# SlowChans.net
KiCad netlist of a schematic drawn in Altium Designer
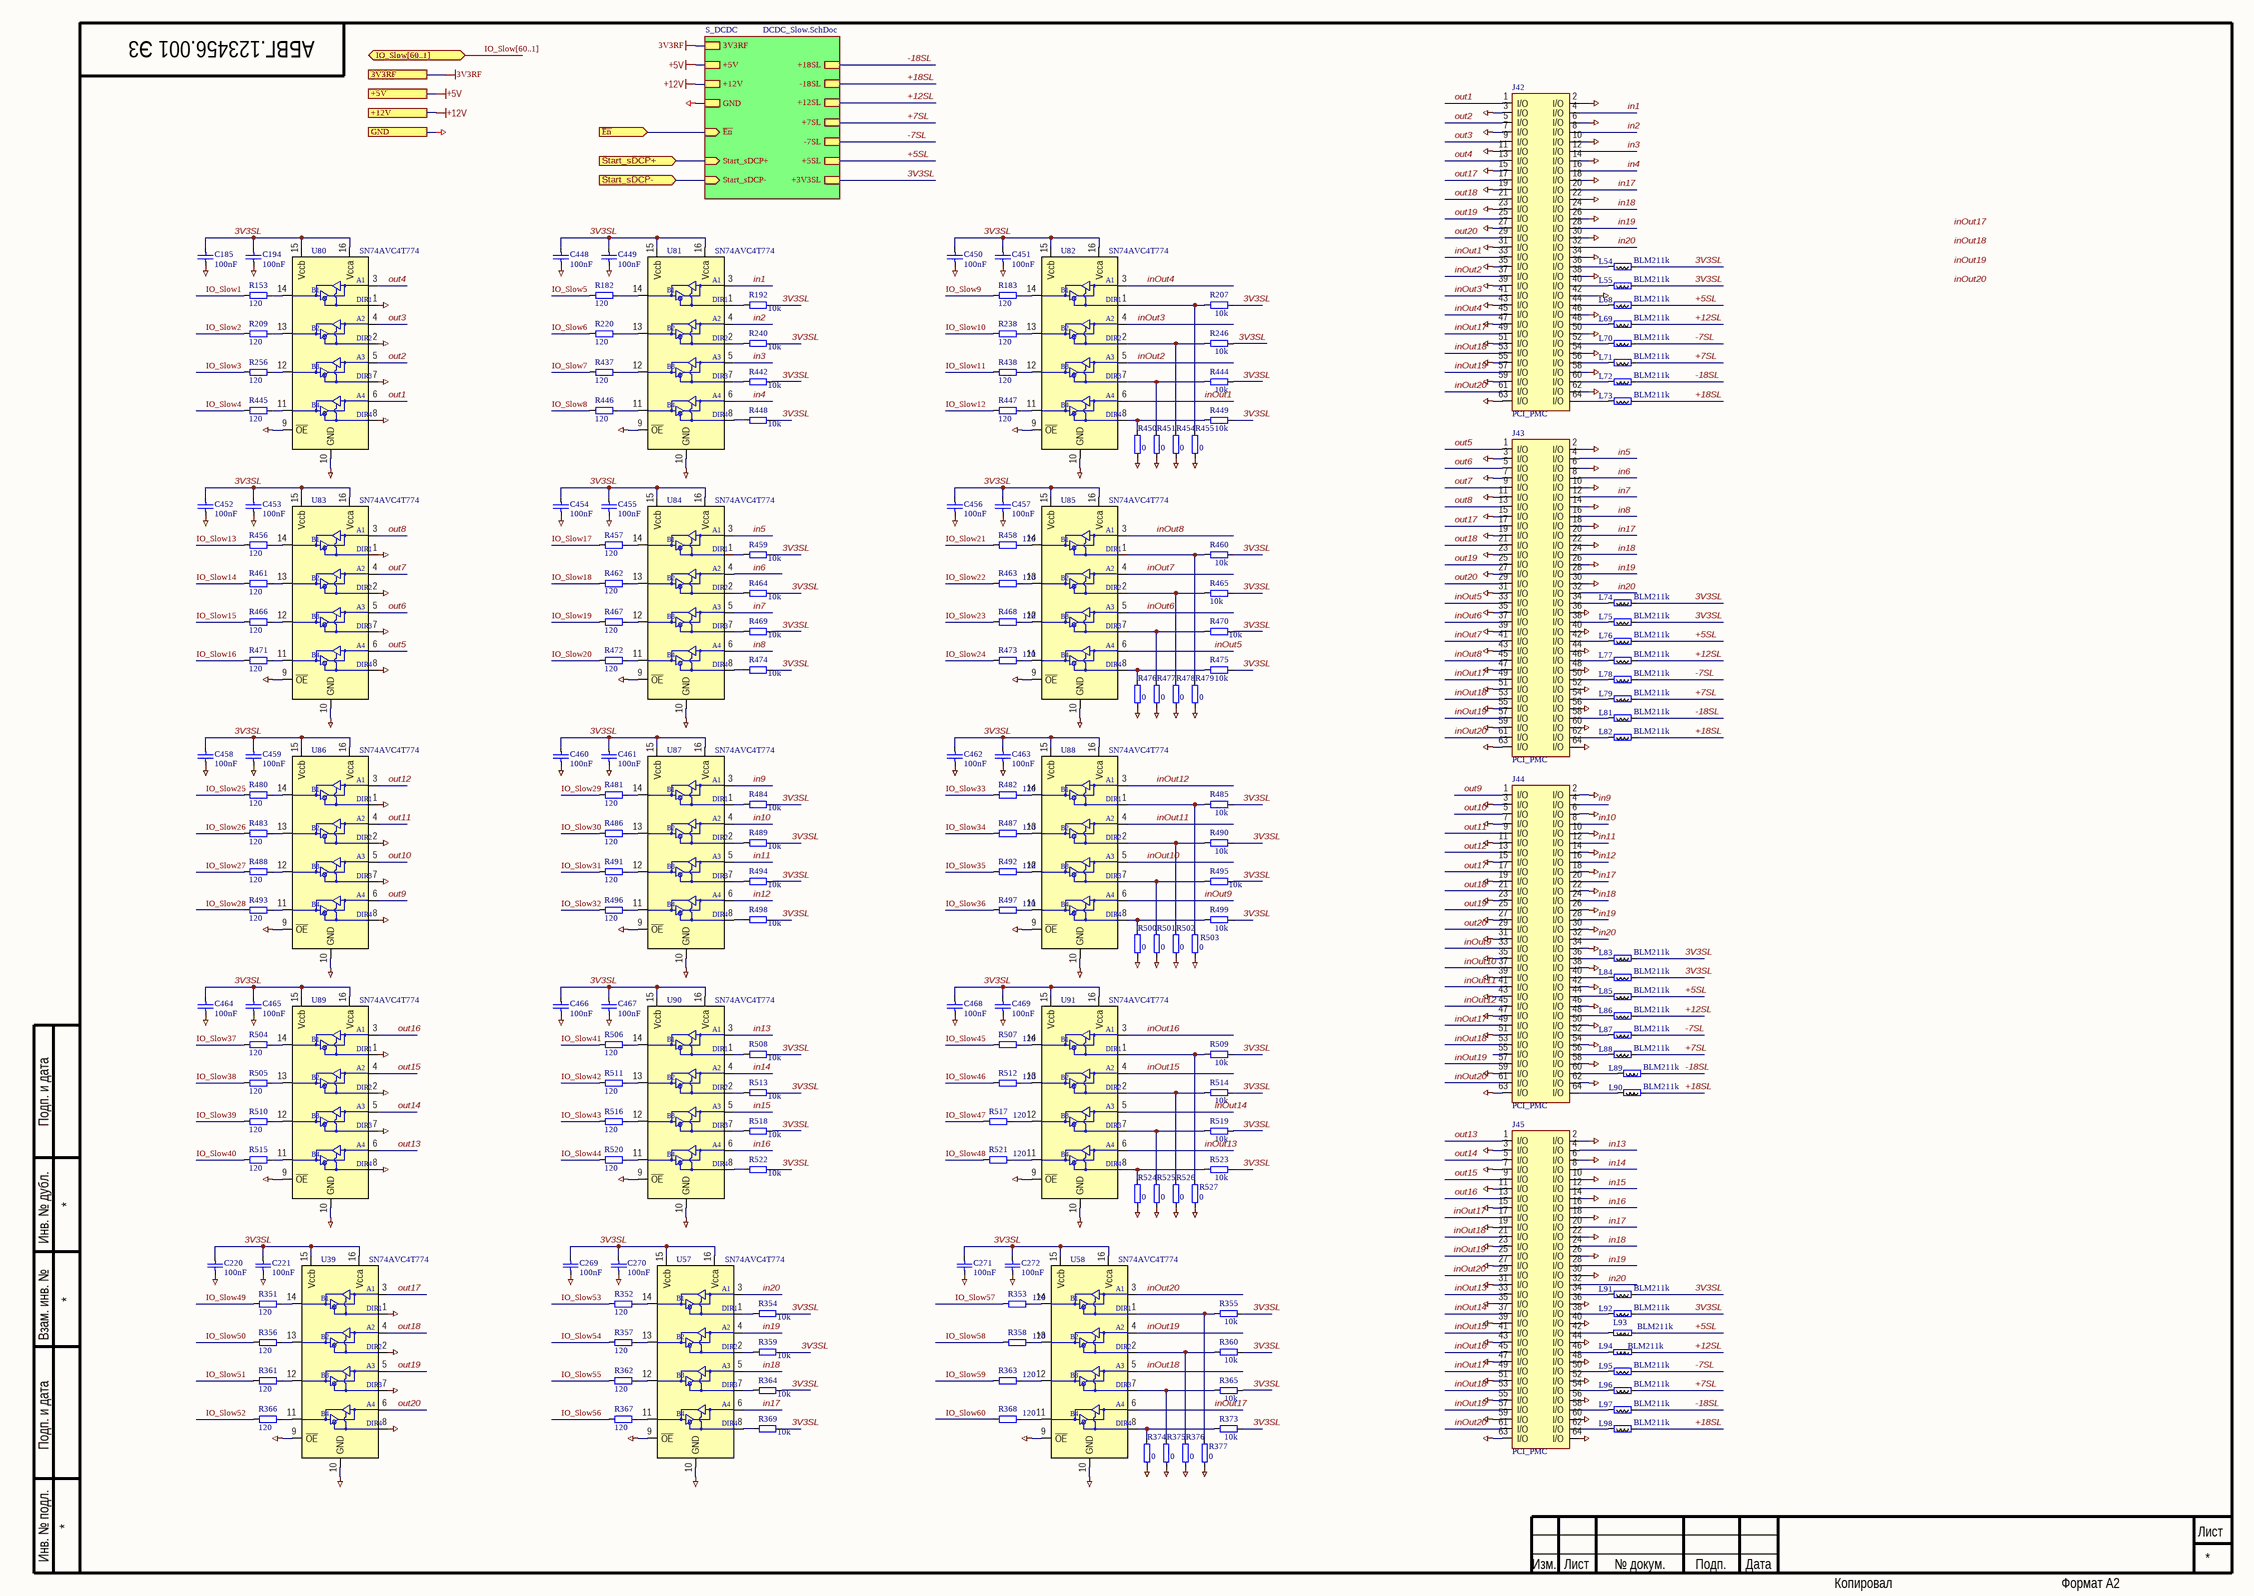
[diagram p0: SlowChans.SchDoc]

(export (version "E")
  (design (tool "Eeschema 10.0.6"))
  (components
    (comp (ref "C185")
      (value "100nF")
      (footprint "SMD0805CAP")
      (description "Чип конденсатор 0805")
      (fields (field (name "VOLTAGE") "25V") (field (name "TOLERANCE") "20%"))
      (libsource (lib "DDSintLib") (part "C0805"))
    )
    (comp (ref "C194")
      (value "100nF")
      (footprint "SMD0805CAP")
      (description "Чип конденсатор 0805")
      (fields (field (name "VOLTAGE") "25V") (field (name "TOLERANCE") "20%"))
      (libsource (lib "DDSintLib") (part "C0805"))
    )
    (comp (ref "C220")
      (value "100nF")
      (footprint "SMD0805CAP")
      (description "Чип конденсатор 0805")
      (fields (field (name "VOLTAGE") "25V") (field (name "TOLERANCE") "20%"))
      (libsource (lib "DDSintLib") (part "C0805"))
    )
    (comp (ref "C221")
      (value "100nF")
      (footprint "SMD0805CAP")
      (description "Чип конденсатор 0805")
      (fields (field (name "VOLTAGE") "25V") (field (name "TOLERANCE") "20%"))
      (libsource (lib "DDSintLib") (part "C0805"))
    )
    (comp (ref "C269")
      (value "100nF")
      (footprint "SMD0805CAP")
      (description "Чип конденсатор 0805")
      (fields (field (name "VOLTAGE") "25V") (field (name "TOLERANCE") "20%"))
      (libsource (lib "DDSintLib") (part "C0805"))
    )
    (comp (ref "C270")
      (value "100nF")
      (footprint "SMD0805CAP")
      (description "Чип конденсатор 0805")
      (fields (field (name "VOLTAGE") "25V") (field (name "TOLERANCE") "20%"))
      (libsource (lib "DDSintLib") (part "C0805"))
    )
    (comp (ref "C271")
      (value "100nF")
      (footprint "SMD0805CAP")
      (description "Чип конденсатор 0805")
      (fields (field (name "VOLTAGE") "25V") (field (name "TOLERANCE") "20%"))
      (libsource (lib "DDSintLib") (part "C0805"))
    )
    (comp (ref "C272")
      (value "100nF")
      (footprint "SMD0805CAP")
      (description "Чип конденсатор 0805")
      (fields (field (name "VOLTAGE") "25V") (field (name "TOLERANCE") "20%"))
      (libsource (lib "DDSintLib") (part "C0805"))
    )
    (comp (ref "C448")
      (value "100nF")
      (footprint "SMD0805CAP")
      (description "Чип конденсатор 0805")
      (fields (field (name "VOLTAGE") "25V") (field (name "TOLERANCE") "20%"))
      (libsource (lib "DDSintLib") (part "C0805"))
    )
    (comp (ref "C449")
      (value "100nF")
      (footprint "SMD0805CAP")
      (description "Чип конденсатор 0805")
      (fields (field (name "VOLTAGE") "25V") (field (name "TOLERANCE") "20%"))
      (libsource (lib "DDSintLib") (part "C0805"))
    )
    (comp (ref "C450")
      (value "100nF")
      (footprint "SMD0805CAP")
      (description "Чип конденсатор 0805")
      (fields (field (name "VOLTAGE") "25V") (field (name "TOLERANCE") "20%"))
      (libsource (lib "DDSintLib") (part "C0805"))
    )
    (comp (ref "C451")
      (value "100nF")
      (footprint "SMD0805CAP")
      (description "Чип конденсатор 0805")
      (fields (field (name "VOLTAGE") "25V") (field (name "TOLERANCE") "20%"))
      (libsource (lib "DDSintLib") (part "C0805"))
    )
    (comp (ref "C452")
      (value "100nF")
      (footprint "SMD0805CAP")
      (description "Чип конденсатор 0805")
      (fields (field (name "VOLTAGE") "25V") (field (name "TOLERANCE") "20%"))
      (libsource (lib "DDSintLib") (part "C0805"))
    )
    (comp (ref "C453")
      (value "100nF")
      (footprint "SMD0805CAP")
      (description "Чип конденсатор 0805")
      (fields (field (name "VOLTAGE") "25V") (field (name "TOLERANCE") "20%"))
      (libsource (lib "DDSintLib") (part "C0805"))
    )
    (comp (ref "C454")
      (value "100nF")
      (footprint "SMD0805CAP")
      (description "Чип конденсатор 0805")
      (fields (field (name "VOLTAGE") "25V") (field (name "TOLERANCE") "20%"))
      (libsource (lib "DDSintLib") (part "C0805"))
    )
    (comp (ref "C455")
      (value "100nF")
      (footprint "SMD0805CAP")
      (description "Чип конденсатор 0805")
      (fields (field (name "VOLTAGE") "25V") (field (name "TOLERANCE") "20%"))
      (libsource (lib "DDSintLib") (part "C0805"))
    )
    (comp (ref "C456")
      (value "100nF")
      (footprint "SMD0805CAP")
      (description "Чип конденсатор 0805")
      (fields (field (name "VOLTAGE") "25V") (field (name "TOLERANCE") "20%"))
      (libsource (lib "DDSintLib") (part "C0805"))
    )
    (comp (ref "C457")
      (value "100nF")
      (footprint "SMD0805CAP")
      (description "Чип конденсатор 0805")
      (fields (field (name "VOLTAGE") "25V") (field (name "TOLERANCE") "20%"))
      (libsource (lib "DDSintLib") (part "C0805"))
    )
    (comp (ref "C458")
      (value "100nF")
      (footprint "SMD0805CAP")
      (description "Чип конденсатор 0805")
      (fields (field (name "VOLTAGE") "25V") (field (name "TOLERANCE") "20%"))
      (libsource (lib "DDSintLib") (part "C0805"))
    )
    (comp (ref "C459")
      (value "100nF")
      (footprint "SMD0805CAP")
      (description "Чип конденсатор 0805")
      (fields (field (name "VOLTAGE") "25V") (field (name "TOLERANCE") "20%"))
      (libsource (lib "DDSintLib") (part "C0805"))
    )
    (comp (ref "C460")
      (value "100nF")
      (footprint "SMD0805CAP")
      (description "Чип конденсатор 0805")
      (fields (field (name "VOLTAGE") "25V") (field (name "TOLERANCE") "20%"))
      (libsource (lib "DDSintLib") (part "C0805"))
    )
    (comp (ref "C461")
      (value "100nF")
      (footprint "SMD0805CAP")
      (description "Чип конденсатор 0805")
      (fields (field (name "VOLTAGE") "25V") (field (name "TOLERANCE") "20%"))
      (libsource (lib "DDSintLib") (part "C0805"))
    )
    (comp (ref "C462")
      (value "100nF")
      (footprint "SMD0805CAP")
      (description "Чип конденсатор 0805")
      (fields (field (name "VOLTAGE") "25V") (field (name "TOLERANCE") "20%"))
      (libsource (lib "DDSintLib") (part "C0805"))
    )
    (comp (ref "C463")
      (value "100nF")
      (footprint "SMD0805CAP")
      (description "Чип конденсатор 0805")
      (fields (field (name "VOLTAGE") "25V") (field (name "TOLERANCE") "20%"))
      (libsource (lib "DDSintLib") (part "C0805"))
    )
    (comp (ref "C464")
      (value "100nF")
      (footprint "SMD0805CAP")
      (description "Чип конденсатор 0805")
      (fields (field (name "VOLTAGE") "25V") (field (name "TOLERANCE") "20%"))
      (libsource (lib "DDSintLib") (part "C0805"))
    )
    (comp (ref "C465")
      (value "100nF")
      (footprint "SMD0805CAP")
      (description "Чип конденсатор 0805")
      (fields (field (name "VOLTAGE") "25V") (field (name "TOLERANCE") "20%"))
      (libsource (lib "DDSintLib") (part "C0805"))
    )
    (comp (ref "C466")
      (value "100nF")
      (footprint "SMD0805CAP")
      (description "Чип конденсатор 0805")
      (fields (field (name "VOLTAGE") "25V") (field (name "TOLERANCE") "20%"))
      (libsource (lib "DDSintLib") (part "C0805"))
    )
    (comp (ref "C467")
      (value "100nF")
      (footprint "SMD0805CAP")
      (description "Чип конденсатор 0805")
      (fields (field (name "VOLTAGE") "25V") (field (name "TOLERANCE") "20%"))
      (libsource (lib "DDSintLib") (part "C0805"))
    )
    (comp (ref "C468")
      (value "100nF")
      (footprint "SMD0805CAP")
      (description "Чип конденсатор 0805")
      (fields (field (name "VOLTAGE") "25V") (field (name "TOLERANCE") "20%"))
      (libsource (lib "DDSintLib") (part "C0805"))
    )
    (comp (ref "C469")
      (value "100nF")
      (footprint "SMD0805CAP")
      (description "Чип конденсатор 0805")
      (fields (field (name "VOLTAGE") "25V") (field (name "TOLERANCE") "20%"))
      (libsource (lib "DDSintLib") (part "C0805"))
    )
    (comp (ref "J42")
      (value "PCI_PMC")
      (footprint "TYCO_120521-1")
      (description "PCI Mezzanine Connector; IEEE 1386 MainBoard")
      (libsource (lib "DDSintLib") (part "PCI_PMC_M"))
    )
    (comp (ref "J43")
      (value "PCI_PMC")
      (footprint "TYCO_120521-1")
      (description "PCI Mezzanine Connector; IEEE 1386 MainBoard")
      (libsource (lib "DDSintLib") (part "PCI_PMC_M"))
    )
    (comp (ref "J44")
      (value "PCI_PMC")
      (footprint "TYCO_120521-1")
      (description "PCI Mezzanine Connector; IEEE 1386 MainBoard")
      (libsource (lib "DDSintLib") (part "PCI_PMC_M"))
    )
    (comp (ref "J45")
      (value "PCI_PMC")
      (footprint "TYCO_120521-1")
      (description "PCI Mezzanine Connector; IEEE 1386 MainBoard")
      (libsource (lib "DDSintLib") (part "PCI_PMC_M"))
    )
    (comp (ref "L54")
      (value "BLM211k")
      (footprint "RESC2012X50N")
      (description "SMD Ferrite bead 0805")
      (libsource (lib "DDSintLib") (part "BLM21"))
    )
    (comp (ref "L55")
      (value "BLM211k")
      (footprint "RESC2012X50N")
      (description "SMD Ferrite bead 0805")
      (libsource (lib "DDSintLib") (part "BLM21"))
    )
    (comp (ref "L68")
      (value "BLM211k")
      (footprint "RESC2012X50N")
      (description "SMD Ferrite bead 0805")
      (libsource (lib "DDSintLib") (part "BLM21"))
    )
    (comp (ref "L69")
      (value "BLM211k")
      (footprint "RESC2012X50N")
      (description "SMD Ferrite bead 0805")
      (libsource (lib "DDSintLib") (part "BLM21"))
    )
    (comp (ref "L70")
      (value "BLM211k")
      (footprint "RESC2012X50N")
      (description "SMD Ferrite bead 0805")
      (libsource (lib "DDSintLib") (part "BLM21"))
    )
    (comp (ref "L71")
      (value "BLM211k")
      (footprint "RESC2012X50N")
      (description "SMD Ferrite bead 0805")
      (libsource (lib "DDSintLib") (part "BLM21"))
    )
    (comp (ref "L72")
      (value "BLM211k")
      (footprint "RESC2012X50N")
      (description "SMD Ferrite bead 0805")
      (libsource (lib "DDSintLib") (part "BLM21"))
    )
    (comp (ref "L73")
      (value "BLM211k")
      (footprint "RESC2012X50N")
      (description "SMD Ferrite bead 0805")
      (libsource (lib "DDSintLib") (part "BLM21"))
    )
    (comp (ref "L74")
      (value "BLM211k")
      (footprint "RESC2012X50N")
      (description "SMD Ferrite bead 0805")
      (libsource (lib "DDSintLib") (part "BLM21"))
    )
    (comp (ref "L75")
      (value "BLM211k")
      (footprint "RESC2012X50N")
      (description "SMD Ferrite bead 0805")
      (libsource (lib "DDSintLib") (part "BLM21"))
    )
    (comp (ref "L76")
      (value "BLM211k")
      (footprint "RESC2012X50N")
      (description "SMD Ferrite bead 0805")
      (libsource (lib "DDSintLib") (part "BLM21"))
    )
    (comp (ref "L77")
      (value "BLM211k")
      (footprint "RESC2012X50N")
      (description "SMD Ferrite bead 0805")
      (libsource (lib "DDSintLib") (part "BLM21"))
    )
    (comp (ref "L78")
      (value "BLM211k")
      (footprint "RESC2012X50N")
      (description "SMD Ferrite bead 0805")
      (libsource (lib "DDSintLib") (part "BLM21"))
    )
    (comp (ref "L79")
      (value "BLM211k")
      (footprint "RESC2012X50N")
      (description "SMD Ferrite bead 0805")
      (libsource (lib "DDSintLib") (part "BLM21"))
    )
    (comp (ref "L81")
      (value "BLM211k")
      (footprint "RESC2012X50N")
      (description "SMD Ferrite bead 0805")
      (libsource (lib "DDSintLib") (part "BLM21"))
    )
    (comp (ref "L82")
      (value "BLM211k")
      (footprint "RESC2012X50N")
      (description "SMD Ferrite bead 0805")
      (libsource (lib "DDSintLib") (part "BLM21"))
    )
    (comp (ref "L83")
      (value "BLM211k")
      (footprint "RESC2012X50N")
      (description "SMD Ferrite bead 0805")
      (libsource (lib "DDSintLib") (part "BLM21"))
    )
    (comp (ref "L84")
      (value "BLM211k")
      (footprint "RESC2012X50N")
      (description "SMD Ferrite bead 0805")
      (libsource (lib "DDSintLib") (part "BLM21"))
    )
    (comp (ref "L85")
      (value "BLM211k")
      (footprint "RESC2012X50N")
      (description "SMD Ferrite bead 0805")
      (libsource (lib "DDSintLib") (part "BLM21"))
    )
    (comp (ref "L86")
      (value "BLM211k")
      (footprint "RESC2012X50N")
      (description "SMD Ferrite bead 0805")
      (libsource (lib "DDSintLib") (part "BLM21"))
    )
    (comp (ref "L87")
      (value "BLM211k")
      (footprint "RESC2012X50N")
      (description "SMD Ferrite bead 0805")
      (libsource (lib "DDSintLib") (part "BLM21"))
    )
    (comp (ref "L88")
      (value "BLM211k")
      (footprint "RESC2012X50N")
      (description "SMD Ferrite bead 0805")
      (libsource (lib "DDSintLib") (part "BLM21"))
    )
    (comp (ref "L89")
      (value "BLM211k")
      (footprint "RESC2012X50N")
      (description "SMD Ferrite bead 0805")
      (libsource (lib "DDSintLib") (part "BLM21"))
    )
    (comp (ref "L90")
      (value "BLM211k")
      (footprint "RESC2012X50N")
      (description "SMD Ferrite bead 0805")
      (libsource (lib "DDSintLib") (part "BLM21"))
    )
    (comp (ref "L91")
      (value "BLM211k")
      (footprint "RESC2012X50N")
      (description "SMD Ferrite bead 0805")
      (libsource (lib "DDSintLib") (part "BLM21"))
    )
    (comp (ref "L92")
      (value "BLM211k")
      (footprint "RESC2012X50N")
      (description "SMD Ferrite bead 0805")
      (libsource (lib "DDSintLib") (part "BLM21"))
    )
    (comp (ref "L93")
      (value "BLM211k")
      (footprint "RESC2012X50N")
      (description "SMD Ferrite bead 0805")
      (libsource (lib "") (part "BLM21_1"))
    )
    (comp (ref "L94")
      (value "BLM211k")
      (footprint "RESC2012X50N")
      (description "SMD Ferrite bead 0805")
      (libsource (lib "") (part "BLM21_1"))
    )
    (comp (ref "L95")
      (value "BLM211k")
      (footprint "RESC2012X50N")
      (description "SMD Ferrite bead 0805")
      (libsource (lib "DDSintLib") (part "BLM21"))
    )
    (comp (ref "L96")
      (value "BLM211k")
      (footprint "RESC2012X50N")
      (description "SMD Ferrite bead 0805")
      (libsource (lib "DDSintLib") (part "BLM21"))
    )
    (comp (ref "L97")
      (value "BLM211k")
      (footprint "RESC2012X50N")
      (description "SMD Ferrite bead 0805")
      (libsource (lib "DDSintLib") (part "BLM21"))
    )
    (comp (ref "L98")
      (value "BLM211k")
      (footprint "RESC2012X50N")
      (description "SMD Ferrite bead 0805")
      (libsource (lib "DDSintLib") (part "BLM21"))
    )
    (comp (ref "R153")
      (value "120")
      (footprint "SMD0805RES")
      (description "Чип резистор 0805")
      (fields (field (name "TOLERANCE") "1%"))
      (libsource (lib "DDSintLib") (part "R0805"))
    )
    (comp (ref "R182")
      (value "120")
      (footprint "SMD0805RES")
      (description "Чип резистор 0805")
      (fields (field (name "TOLERANCE") "1%"))
      (libsource (lib "DDSintLib") (part "R0805"))
    )
    (comp (ref "R183")
      (value "120")
      (footprint "SMD0805RES")
      (description "Чип резистор 0805")
      (fields (field (name "TOLERANCE") "1%"))
      (libsource (lib "DDSintLib") (part "R0805"))
    )
    (comp (ref "R192")
      (value "10k")
      (footprint "SMD0805RES")
      (description "Чип резистор 0805")
      (fields (field (name "TOLERANCE") "1%"))
      (libsource (lib "DDSintLib") (part "R0805"))
    )
    (comp (ref "R207")
      (value "10k")
      (footprint "SMD0805RES")
      (description "Чип резистор 0805")
      (fields (field (name "TOLERANCE") "1%"))
      (libsource (lib "DDSintLib") (part "R0805"))
    )
    (comp (ref "R209")
      (value "120")
      (footprint "SMD0805RES")
      (description "Чип резистор 0805")
      (fields (field (name "TOLERANCE") "1%"))
      (libsource (lib "DDSintLib") (part "R0805"))
    )
    (comp (ref "R220")
      (value "120")
      (footprint "SMD0805RES")
      (description "Чип резистор 0805")
      (fields (field (name "TOLERANCE") "1%"))
      (libsource (lib "DDSintLib") (part "R0805"))
    )
    (comp (ref "R238")
      (value "120")
      (footprint "SMD0805RES")
      (description "Чип резистор 0805")
      (fields (field (name "TOLERANCE") "1%"))
      (libsource (lib "DDSintLib") (part "R0805"))
    )
    (comp (ref "R240")
      (value "10k")
      (footprint "SMD0805RES")
      (description "Чип резистор 0805")
      (fields (field (name "TOLERANCE") "1%"))
      (libsource (lib "DDSintLib") (part "R0805"))
    )
    (comp (ref "R246")
      (value "10k")
      (footprint "SMD0805RES")
      (description "Чип резистор 0805")
      (fields (field (name "TOLERANCE") "1%"))
      (libsource (lib "DDSintLib") (part "R0805"))
    )
    (comp (ref "R256")
      (value "120")
      (footprint "SMD0805RES")
      (description "Чип резистор 0805")
      (fields (field (name "TOLERANCE") "1%"))
      (libsource (lib "DDSintLib") (part "R0805"))
    )
    (comp (ref "R351")
      (value "120")
      (footprint "SMD0805RES")
      (description "Чип резистор 0805")
      (fields (field (name "TOLERANCE") "1%"))
      (libsource (lib "DDSintLib") (part "R0805"))
    )
    (comp (ref "R352")
      (value "120")
      (footprint "SMD0805RES")
      (description "Чип резистор 0805")
      (fields (field (name "TOLERANCE") "1%"))
      (libsource (lib "DDSintLib") (part "R0805"))
    )
    (comp (ref "R353")
      (value "120")
      (footprint "SMD0805RES")
      (description "Чип резистор 0805")
      (fields (field (name "TOLERANCE") "1%"))
      (libsource (lib "DDSintLib") (part "R0805"))
    )
    (comp (ref "R354")
      (value "10k")
      (footprint "SMD0805RES")
      (description "Чип резистор 0805")
      (fields (field (name "TOLERANCE") "1%"))
      (libsource (lib "DDSintLib") (part "R0805"))
    )
    (comp (ref "R355")
      (value "10k")
      (footprint "SMD0805RES")
      (description "Чип резистор 0805")
      (fields (field (name "TOLERANCE") "1%"))
      (libsource (lib "DDSintLib") (part "R0805"))
    )
    (comp (ref "R356")
      (value "120")
      (footprint "SMD0805RES")
      (description "Чип резистор 0805")
      (fields (field (name "TOLERANCE") "1%"))
      (libsource (lib "DDSintLib") (part "R0805"))
    )
    (comp (ref "R357")
      (value "120")
      (footprint "SMD0805RES")
      (description "Чип резистор 0805")
      (fields (field (name "TOLERANCE") "1%"))
      (libsource (lib "DDSintLib") (part "R0805"))
    )
    (comp (ref "R358")
      (value "120")
      (footprint "SMD0805RES")
      (description "Чип резистор 0805")
      (fields (field (name "TOLERANCE") "1%"))
      (libsource (lib "DDSintLib") (part "R0805"))
    )
    (comp (ref "R359")
      (value "10k")
      (footprint "SMD0805RES")
      (description "Чип резистор 0805")
      (fields (field (name "TOLERANCE") "1%"))
      (libsource (lib "DDSintLib") (part "R0805"))
    )
    (comp (ref "R360")
      (value "10k")
      (footprint "SMD0805RES")
      (description "Чип резистор 0805")
      (fields (field (name "TOLERANCE") "1%"))
      (libsource (lib "DDSintLib") (part "R0805"))
    )
    (comp (ref "R361")
      (value "120")
      (footprint "SMD0805RES")
      (description "Чип резистор 0805")
      (fields (field (name "TOLERANCE") "1%"))
      (libsource (lib "DDSintLib") (part "R0805"))
    )
    (comp (ref "R362")
      (value "120")
      (footprint "SMD0805RES")
      (description "Чип резистор 0805")
      (fields (field (name "TOLERANCE") "1%"))
      (libsource (lib "DDSintLib") (part "R0805"))
    )
    (comp (ref "R363")
      (value "120")
      (footprint "SMD0805RES")
      (description "Чип резистор 0805")
      (fields (field (name "TOLERANCE") "1%"))
      (libsource (lib "DDSintLib") (part "R0805"))
    )
    (comp (ref "R364")
      (value "10k")
      (footprint "SMD0805RES")
      (description "Чип резистор 0805")
      (fields (field (name "TOLERANCE") "1%"))
      (libsource (lib "DDSintLib") (part "R0805"))
    )
    (comp (ref "R365")
      (value "10k")
      (footprint "SMD0805RES")
      (description "Чип резистор 0805")
      (fields (field (name "TOLERANCE") "1%"))
      (libsource (lib "DDSintLib") (part "R0805"))
    )
    (comp (ref "R366")
      (value "120")
      (footprint "SMD0805RES")
      (description "Чип резистор 0805")
      (fields (field (name "TOLERANCE") "1%"))
      (libsource (lib "DDSintLib") (part "R0805"))
    )
    (comp (ref "R367")
      (value "120")
      (footprint "SMD0805RES")
      (description "Чип резистор 0805")
      (fields (field (name "TOLERANCE") "1%"))
      (libsource (lib "DDSintLib") (part "R0805"))
    )
    (comp (ref "R368")
      (value "120")
      (footprint "SMD0805RES")
      (description "Чип резистор 0805")
      (fields (field (name "TOLERANCE") "1%"))
      (libsource (lib "DDSintLib") (part "R0805"))
    )
    (comp (ref "R369")
      (value "10k")
      (footprint "SMD0805RES")
      (description "Чип резистор 0805")
      (fields (field (name "TOLERANCE") "1%"))
      (libsource (lib "DDSintLib") (part "R0805"))
    )
    (comp (ref "R373")
      (value "10k")
      (footprint "SMD0805RES")
      (description "Чип резистор 0805")
      (fields (field (name "TOLERANCE") "1%"))
      (libsource (lib "DDSintLib") (part "R0805"))
    )
    (comp (ref "R374")
      (value "0")
      (footprint "SMD0805RES")
      (description "Чип резистор 0805")
      (fields (field (name "TOLERANCE") "1%"))
      (libsource (lib "DDSintLib") (part "R0805"))
    )
    (comp (ref "R375")
      (value "0")
      (footprint "SMD0805RES")
      (description "Чип резистор 0805")
      (fields (field (name "TOLERANCE") "1%"))
      (libsource (lib "DDSintLib") (part "R0805"))
    )
    (comp (ref "R376")
      (value "0")
      (footprint "SMD0805RES")
      (description "Чип резистор 0805")
      (fields (field (name "TOLERANCE") "1%"))
      (libsource (lib "DDSintLib") (part "R0805"))
    )
    (comp (ref "R377")
      (value "0")
      (footprint "SMD0805RES")
      (description "Чип резистор 0805")
      (fields (field (name "TOLERANCE") "1%"))
      (libsource (lib "DDSintLib") (part "R0805"))
    )
    (comp (ref "R437")
      (value "120")
      (footprint "SMD0805RES")
      (description "Чип резистор 0805")
      (fields (field (name "TOLERANCE") "1%"))
      (libsource (lib "DDSintLib") (part "R0805"))
    )
    (comp (ref "R438")
      (value "120")
      (footprint "SMD0805RES")
      (description "Чип резистор 0805")
      (fields (field (name "TOLERANCE") "1%"))
      (libsource (lib "DDSintLib") (part "R0805"))
    )
    (comp (ref "R442")
      (value "10k")
      (footprint "SMD0805RES")
      (description "Чип резистор 0805")
      (fields (field (name "TOLERANCE") "1%"))
      (libsource (lib "DDSintLib") (part "R0805"))
    )
    (comp (ref "R444")
      (value "10k")
      (footprint "SMD0805RES")
      (description "Чип резистор 0805")
      (fields (field (name "TOLERANCE") "1%"))
      (libsource (lib "DDSintLib") (part "R0805"))
    )
    (comp (ref "R445")
      (value "120")
      (footprint "SMD0805RES")
      (description "Чип резистор 0805")
      (fields (field (name "TOLERANCE") "1%"))
      (libsource (lib "DDSintLib") (part "R0805"))
    )
    (comp (ref "R446")
      (value "120")
      (footprint "SMD0805RES")
      (description "Чип резистор 0805")
      (fields (field (name "TOLERANCE") "1%"))
      (libsource (lib "DDSintLib") (part "R0805"))
    )
    (comp (ref "R447")
      (value "120")
      (footprint "SMD0805RES")
      (description "Чип резистор 0805")
      (fields (field (name "TOLERANCE") "1%"))
      (libsource (lib "DDSintLib") (part "R0805"))
    )
    (comp (ref "R448")
      (value "10k")
      (footprint "SMD0805RES")
      (description "Чип резистор 0805")
      (fields (field (name "TOLERANCE") "1%"))
      (libsource (lib "DDSintLib") (part "R0805"))
    )
    (comp (ref "R449")
      (value "10k")
      (footprint "SMD0805RES")
      (description "Чип резистор 0805")
      (fields (field (name "TOLERANCE") "1%"))
      (libsource (lib "DDSintLib") (part "R0805"))
    )
    (comp (ref "R450")
      (value "0")
      (footprint "SMD0805RES")
      (description "Чип резистор 0805")
      (fields (field (name "TOLERANCE") "1%"))
      (libsource (lib "DDSintLib") (part "R0805"))
    )
    (comp (ref "R451")
      (value "0")
      (footprint "SMD0805RES")
      (description "Чип резистор 0805")
      (fields (field (name "TOLERANCE") "1%"))
      (libsource (lib "DDSintLib") (part "R0805"))
    )
    (comp (ref "R454")
      (value "0")
      (footprint "SMD0805RES")
      (description "Чип резистор 0805")
      (fields (field (name "TOLERANCE") "1%"))
      (libsource (lib "DDSintLib") (part "R0805"))
    )
    (comp (ref "R455")
      (value "0")
      (footprint "SMD0805RES")
      (description "Чип резистор 0805")
      (fields (field (name "TOLERANCE") "1%"))
      (libsource (lib "DDSintLib") (part "R0805"))
    )
    (comp (ref "R456")
      (value "120")
      (footprint "SMD0805RES")
      (description "Чип резистор 0805")
      (fields (field (name "TOLERANCE") "1%"))
      (libsource (lib "DDSintLib") (part "R0805"))
    )
    (comp (ref "R457")
      (value "120")
      (footprint "SMD0805RES")
      (description "Чип резистор 0805")
      (fields (field (name "TOLERANCE") "1%"))
      (libsource (lib "DDSintLib") (part "R0805"))
    )
    (comp (ref "R458")
      (value "120")
      (footprint "SMD0805RES")
      (description "Чип резистор 0805")
      (fields (field (name "TOLERANCE") "1%"))
      (libsource (lib "DDSintLib") (part "R0805"))
    )
    (comp (ref "R459")
      (value "10k")
      (footprint "SMD0805RES")
      (description "Чип резистор 0805")
      (fields (field (name "TOLERANCE") "1%"))
      (libsource (lib "DDSintLib") (part "R0805"))
    )
    (comp (ref "R460")
      (value "10k")
      (footprint "SMD0805RES")
      (description "Чип резистор 0805")
      (fields (field (name "TOLERANCE") "1%"))
      (libsource (lib "DDSintLib") (part "R0805"))
    )
    (comp (ref "R461")
      (value "120")
      (footprint "SMD0805RES")
      (description "Чип резистор 0805")
      (fields (field (name "TOLERANCE") "1%"))
      (libsource (lib "DDSintLib") (part "R0805"))
    )
    (comp (ref "R462")
      (value "120")
      (footprint "SMD0805RES")
      (description "Чип резистор 0805")
      (fields (field (name "TOLERANCE") "1%"))
      (libsource (lib "DDSintLib") (part "R0805"))
    )
    (comp (ref "R463")
      (value "120")
      (footprint "SMD0805RES")
      (description "Чип резистор 0805")
      (fields (field (name "TOLERANCE") "1%"))
      (libsource (lib "DDSintLib") (part "R0805"))
    )
    (comp (ref "R464")
      (value "10k")
      (footprint "SMD0805RES")
      (description "Чип резистор 0805")
      (fields (field (name "TOLERANCE") "1%"))
      (libsource (lib "DDSintLib") (part "R0805"))
    )
    (comp (ref "R465")
      (value "10k")
      (footprint "SMD0805RES")
      (description "Чип резистор 0805")
      (fields (field (name "TOLERANCE") "1%"))
      (libsource (lib "DDSintLib") (part "R0805"))
    )
    (comp (ref "R466")
      (value "120")
      (footprint "SMD0805RES")
      (description "Чип резистор 0805")
      (fields (field (name "TOLERANCE") "1%"))
      (libsource (lib "DDSintLib") (part "R0805"))
    )
    (comp (ref "R467")
      (value "120")
      (footprint "SMD0805RES")
      (description "Чип резистор 0805")
      (fields (field (name "TOLERANCE") "1%"))
      (libsource (lib "DDSintLib") (part "R0805"))
    )
    (comp (ref "R468")
      (value "120")
      (footprint "SMD0805RES")
      (description "Чип резистор 0805")
      (fields (field (name "TOLERANCE") "1%"))
      (libsource (lib "DDSintLib") (part "R0805"))
    )
    (comp (ref "R469")
      (value "10k")
      (footprint "SMD0805RES")
      (description "Чип резистор 0805")
      (fields (field (name "TOLERANCE") "1%"))
      (libsource (lib "DDSintLib") (part "R0805"))
    )
    (comp (ref "R470")
      (value "10k")
      (footprint "SMD0805RES")
      (description "Чип резистор 0805")
      (fields (field (name "TOLERANCE") "1%"))
      (libsource (lib "DDSintLib") (part "R0805"))
    )
    (comp (ref "R471")
      (value "120")
      (footprint "SMD0805RES")
      (description "Чип резистор 0805")
      (fields (field (name "TOLERANCE") "1%"))
      (libsource (lib "DDSintLib") (part "R0805"))
    )
    (comp (ref "R472")
      (value "120")
      (footprint "SMD0805RES")
      (description "Чип резистор 0805")
      (fields (field (name "TOLERANCE") "1%"))
      (libsource (lib "DDSintLib") (part "R0805"))
    )
    (comp (ref "R473")
      (value "120")
      (footprint "SMD0805RES")
      (description "Чип резистор 0805")
      (fields (field (name "TOLERANCE") "1%"))
      (libsource (lib "DDSintLib") (part "R0805"))
    )
    (comp (ref "R474")
      (value "10k")
      (footprint "SMD0805RES")
      (description "Чип резистор 0805")
      (fields (field (name "TOLERANCE") "1%"))
      (libsource (lib "DDSintLib") (part "R0805"))
    )
    (comp (ref "R475")
      (value "10k")
      (footprint "SMD0805RES")
      (description "Чип резистор 0805")
      (fields (field (name "TOLERANCE") "1%"))
      (libsource (lib "DDSintLib") (part "R0805"))
    )
    (comp (ref "R476")
      (value "0")
      (footprint "SMD0805RES")
      (description "Чип резистор 0805")
      (fields (field (name "TOLERANCE") "1%"))
      (libsource (lib "DDSintLib") (part "R0805"))
    )
    (comp (ref "R477")
      (value "0")
      (footprint "SMD0805RES")
      (description "Чип резистор 0805")
      (fields (field (name "TOLERANCE") "1%"))
      (libsource (lib "DDSintLib") (part "R0805"))
    )
    (comp (ref "R478")
      (value "0")
      (footprint "SMD0805RES")
      (description "Чип резистор 0805")
      (fields (field (name "TOLERANCE") "1%"))
      (libsource (lib "DDSintLib") (part "R0805"))
    )
    (comp (ref "R479")
      (value "0")
      (footprint "SMD0805RES")
      (description "Чип резистор 0805")
      (fields (field (name "TOLERANCE") "1%"))
      (libsource (lib "DDSintLib") (part "R0805"))
    )
    (comp (ref "R480")
      (value "120")
      (footprint "SMD0805RES")
      (description "Чип резистор 0805")
      (fields (field (name "TOLERANCE") "1%"))
      (libsource (lib "DDSintLib") (part "R0805"))
    )
    (comp (ref "R481")
      (value "120")
      (footprint "SMD0805RES")
      (description "Чип резистор 0805")
      (fields (field (name "TOLERANCE") "1%"))
      (libsource (lib "DDSintLib") (part "R0805"))
    )
    (comp (ref "R482")
      (value "120")
      (footprint "SMD0805RES")
      (description "Чип резистор 0805")
      (fields (field (name "TOLERANCE") "1%"))
      (libsource (lib "DDSintLib") (part "R0805"))
    )
    (comp (ref "R483")
      (value "120")
      (footprint "SMD0805RES")
      (description "Чип резистор 0805")
      (fields (field (name "TOLERANCE") "1%"))
      (libsource (lib "DDSintLib") (part "R0805"))
    )
    (comp (ref "R484")
      (value "10k")
      (footprint "SMD0805RES")
      (description "Чип резистор 0805")
      (fields (field (name "TOLERANCE") "1%"))
      (libsource (lib "DDSintLib") (part "R0805"))
    )
    (comp (ref "R485")
      (value "10k")
      (footprint "SMD0805RES")
      (description "Чип резистор 0805")
      (fields (field (name "TOLERANCE") "1%"))
      (libsource (lib "DDSintLib") (part "R0805"))
    )
    (comp (ref "R486")
      (value "120")
      (footprint "SMD0805RES")
      (description "Чип резистор 0805")
      (fields (field (name "TOLERANCE") "1%"))
      (libsource (lib "DDSintLib") (part "R0805"))
    )
    (comp (ref "R487")
      (value "120")
      (footprint "SMD0805RES")
      (description "Чип резистор 0805")
      (fields (field (name "TOLERANCE") "1%"))
      (libsource (lib "DDSintLib") (part "R0805"))
    )
    (comp (ref "R488")
      (value "120")
      (footprint "SMD0805RES")
      (description "Чип резистор 0805")
      (fields (field (name "TOLERANCE") "1%"))
      (libsource (lib "DDSintLib") (part "R0805"))
    )
    (comp (ref "R489")
      (value "10k")
      (footprint "SMD0805RES")
      (description "Чип резистор 0805")
      (fields (field (name "TOLERANCE") "1%"))
      (libsource (lib "DDSintLib") (part "R0805"))
    )
    (comp (ref "R490")
      (value "10k")
      (footprint "SMD0805RES")
      (description "Чип резистор 0805")
      (fields (field (name "TOLERANCE") "1%"))
      (libsource (lib "DDSintLib") (part "R0805"))
    )
    (comp (ref "R491")
      (value "120")
      (footprint "SMD0805RES")
      (description "Чип резистор 0805")
      (fields (field (name "TOLERANCE") "1%"))
      (libsource (lib "DDSintLib") (part "R0805"))
    )
    (comp (ref "R492")
      (value "120")
      (footprint "SMD0805RES")
      (description "Чип резистор 0805")
      (fields (field (name "TOLERANCE") "1%"))
      (libsource (lib "DDSintLib") (part "R0805"))
    )
    (comp (ref "R493")
      (value "120")
      (footprint "SMD0805RES")
      (description "Чип резистор 0805")
      (fields (field (name "TOLERANCE") "1%"))
      (libsource (lib "DDSintLib") (part "R0805"))
    )
    (comp (ref "R494")
      (value "10k")
      (footprint "SMD0805RES")
      (description "Чип резистор 0805")
      (fields (field (name "TOLERANCE") "1%"))
      (libsource (lib "DDSintLib") (part "R0805"))
    )
    (comp (ref "R495")
      (value "10k")
      (footprint "SMD0805RES")
      (description "Чип резистор 0805")
      (fields (field (name "TOLERANCE") "1%"))
      (libsource (lib "DDSintLib") (part "R0805"))
    )
    (comp (ref "R496")
      (value "120")
      (footprint "SMD0805RES")
      (description "Чип резистор 0805")
      (fields (field (name "TOLERANCE") "1%"))
      (libsource (lib "DDSintLib") (part "R0805"))
    )
    (comp (ref "R497")
      (value "120")
      (footprint "SMD0805RES")
      (description "Чип резистор 0805")
      (fields (field (name "TOLERANCE") "1%"))
      (libsource (lib "DDSintLib") (part "R0805"))
    )
    (comp (ref "R498")
      (value "10k")
      (footprint "SMD0805RES")
      (description "Чип резистор 0805")
      (fields (field (name "TOLERANCE") "1%"))
      (libsource (lib "DDSintLib") (part "R0805"))
    )
    (comp (ref "R499")
      (value "10k")
      (footprint "SMD0805RES")
      (description "Чип резистор 0805")
      (fields (field (name "TOLERANCE") "1%"))
      (libsource (lib "DDSintLib") (part "R0805"))
    )
    (comp (ref "R500")
      (value "0")
      (footprint "SMD0805RES")
      (description "Чип резистор 0805")
      (fields (field (name "TOLERANCE") "1%"))
      (libsource (lib "DDSintLib") (part "R0805"))
    )
    (comp (ref "R501")
      (value "0")
      (footprint "SMD0805RES")
      (description "Чип резистор 0805")
      (fields (field (name "TOLERANCE") "1%"))
      (libsource (lib "DDSintLib") (part "R0805"))
    )
    (comp (ref "R502")
      (value "0")
      (footprint "SMD0805RES")
      (description "Чип резистор 0805")
      (fields (field (name "TOLERANCE") "1%"))
      (libsource (lib "DDSintLib") (part "R0805"))
    )
    (comp (ref "R503")
      (value "0")
      (footprint "SMD0805RES")
      (description "Чип резистор 0805")
      (fields (field (name "TOLERANCE") "1%"))
      (libsource (lib "DDSintLib") (part "R0805"))
    )
    (comp (ref "R504")
      (value "120")
      (footprint "SMD0805RES")
      (description "Чип резистор 0805")
      (fields (field (name "TOLERANCE") "1%"))
      (libsource (lib "DDSintLib") (part "R0805"))
    )
    (comp (ref "R505")
      (value "120")
      (footprint "SMD0805RES")
      (description "Чип резистор 0805")
      (fields (field (name "TOLERANCE") "1%"))
      (libsource (lib "DDSintLib") (part "R0805"))
    )
    (comp (ref "R506")
      (value "120")
      (footprint "SMD0805RES")
      (description "Чип резистор 0805")
      (fields (field (name "TOLERANCE") "1%"))
      (libsource (lib "DDSintLib") (part "R0805"))
    )
    (comp (ref "R507")
      (value "120")
      (footprint "SMD0805RES")
      (description "Чип резистор 0805")
      (fields (field (name "TOLERANCE") "1%"))
      (libsource (lib "DDSintLib") (part "R0805"))
    )
    (comp (ref "R508")
      (value "10k")
      (footprint "SMD0805RES")
      (description "Чип резистор 0805")
      (fields (field (name "TOLERANCE") "1%"))
      (libsource (lib "DDSintLib") (part "R0805"))
    )
    (comp (ref "R509")
      (value "10k")
      (footprint "SMD0805RES")
      (description "Чип резистор 0805")
      (fields (field (name "TOLERANCE") "1%"))
      (libsource (lib "DDSintLib") (part "R0805"))
    )
    (comp (ref "R510")
      (value "120")
      (footprint "SMD0805RES")
      (description "Чип резистор 0805")
      (fields (field (name "TOLERANCE") "1%"))
      (libsource (lib "DDSintLib") (part "R0805"))
    )
    (comp (ref "R511")
      (value "120")
      (footprint "SMD0805RES")
      (description "Чип резистор 0805")
      (fields (field (name "TOLERANCE") "1%"))
      (libsource (lib "DDSintLib") (part "R0805"))
    )
    (comp (ref "R512")
      (value "120")
      (footprint "SMD0805RES")
      (description "Чип резистор 0805")
      (fields (field (name "TOLERANCE") "1%"))
      (libsource (lib "DDSintLib") (part "R0805"))
    )
    (comp (ref "R513")
      (value "10k")
      (footprint "SMD0805RES")
      (description "Чип резистор 0805")
      (fields (field (name "TOLERANCE") "1%"))
      (libsource (lib "DDSintLib") (part "R0805"))
    )
    (comp (ref "R514")
      (value "10k")
      (footprint "SMD0805RES")
      (description "Чип резистор 0805")
      (fields (field (name "TOLERANCE") "1%"))
      (libsource (lib "DDSintLib") (part "R0805"))
    )
    (comp (ref "R515")
      (value "120")
      (footprint "SMD0805RES")
      (description "Чип резистор 0805")
      (fields (field (name "TOLERANCE") "1%"))
      (libsource (lib "DDSintLib") (part "R0805"))
    )
    (comp (ref "R516")
      (value "120")
      (footprint "SMD0805RES")
      (description "Чип резистор 0805")
      (fields (field (name "TOLERANCE") "1%"))
      (libsource (lib "DDSintLib") (part "R0805"))
    )
    (comp (ref "R517")
      (value "120")
      (footprint "SMD0805RES")
      (description "Чип резистор 0805")
      (fields (field (name "TOLERANCE") "1%"))
      (libsource (lib "DDSintLib") (part "R0805"))
    )
    (comp (ref "R518")
      (value "10k")
      (footprint "SMD0805RES")
      (description "Чип резистор 0805")
      (fields (field (name "TOLERANCE") "1%"))
      (libsource (lib "DDSintLib") (part "R0805"))
    )
    (comp (ref "R519")
      (value "10k")
      (footprint "SMD0805RES")
      (description "Чип резистор 0805")
      (fields (field (name "TOLERANCE") "1%"))
      (libsource (lib "DDSintLib") (part "R0805"))
    )
    (comp (ref "R520")
      (value "120")
      (footprint "SMD0805RES")
      (description "Чип резистор 0805")
      (fields (field (name "TOLERANCE") "1%"))
      (libsource (lib "DDSintLib") (part "R0805"))
    )
    (comp (ref "R521")
      (value "120")
      (footprint "SMD0805RES")
      (description "Чип резистор 0805")
      (fields (field (name "TOLERANCE") "1%"))
      (libsource (lib "DDSintLib") (part "R0805"))
    )
    (comp (ref "R522")
      (value "10k")
      (footprint "SMD0805RES")
      (description "Чип резистор 0805")
      (fields (field (name "TOLERANCE") "1%"))
      (libsource (lib "DDSintLib") (part "R0805"))
    )
    (comp (ref "R523")
      (value "10k")
      (footprint "SMD0805RES")
      (description "Чип резистор 0805")
      (fields (field (name "TOLERANCE") "1%"))
      (libsource (lib "DDSintLib") (part "R0805"))
    )
    (comp (ref "R524")
      (value "0")
      (footprint "SMD0805RES")
      (description "Чип резистор 0805")
      (fields (field (name "TOLERANCE") "1%"))
      (libsource (lib "DDSintLib") (part "R0805"))
    )
    (comp (ref "R525")
      (value "0")
      (footprint "SMD0805RES")
      (description "Чип резистор 0805")
      (fields (field (name "TOLERANCE") "1%"))
      (libsource (lib "DDSintLib") (part "R0805"))
    )
    (comp (ref "R526")
      (value "0")
      (footprint "SMD0805RES")
      (description "Чип резистор 0805")
      (fields (field (name "TOLERANCE") "1%"))
      (libsource (lib "DDSintLib") (part "R0805"))
    )
    (comp (ref "R527")
      (value "0")
      (footprint "SMD0805RES")
      (description "Чип резистор 0805")
      (fields (field (name "TOLERANCE") "1%"))
      (libsource (lib "DDSintLib") (part "R0805"))
    )
    (comp (ref "U39")
      (value "SN74AVC4T774")
      (footprint "TSSOP-16")
      (description "Двунаправленный буфер")
      (fields (field (name "VOLTAGE") "1V1.. 3.6V  I/Os are 4.6-V Tolerant"))
      (libsource (lib "DDS1") (part "SN74AVC4T774"))
    )
    (comp (ref "U57")
      (value "SN74AVC4T774")
      (footprint "TSSOP-16")
      (description "Двунаправленный буфер")
      (fields (field (name "VOLTAGE") "1V1.. 3.6V  I/Os are 4.6-V Tolerant"))
      (libsource (lib "DDS1") (part "SN74AVC4T774"))
    )
    (comp (ref "U58")
      (value "SN74AVC4T774")
      (footprint "TSSOP-16")
      (description "Двунаправленный буфер")
      (fields (field (name "VOLTAGE") "1V1.. 3.6V  I/Os are 4.6-V Tolerant"))
      (libsource (lib "DDS1") (part "SN74AVC4T774"))
    )
    (comp (ref "U80")
      (value "SN74AVC4T774")
      (footprint "TSSOP-16")
      (description "Двунаправленный буфер")
      (fields (field (name "VOLTAGE") "1V1.. 3.6V  I/Os are 4.6-V Tolerant"))
      (libsource (lib "DDS1") (part "SN74AVC4T774"))
    )
    (comp (ref "U81")
      (value "SN74AVC4T774")
      (footprint "TSSOP-16")
      (description "Двунаправленный буфер")
      (fields (field (name "VOLTAGE") "1V1.. 3.6V  I/Os are 4.6-V Tolerant"))
      (libsource (lib "DDS1") (part "SN74AVC4T774"))
    )
    (comp (ref "U82")
      (value "SN74AVC4T774")
      (footprint "TSSOP-16")
      (description "Двунаправленный буфер")
      (fields (field (name "VOLTAGE") "1V1.. 3.6V  I/Os are 4.6-V Tolerant"))
      (libsource (lib "DDS1") (part "SN74AVC4T774"))
    )
    (comp (ref "U83")
      (value "SN74AVC4T774")
      (footprint "TSSOP-16")
      (description "Двунаправленный буфер")
      (fields (field (name "VOLTAGE") "1V1.. 3.6V  I/Os are 4.6-V Tolerant"))
      (libsource (lib "DDS1") (part "SN74AVC4T774"))
    )
    (comp (ref "U84")
      (value "SN74AVC4T774")
      (footprint "TSSOP-16")
      (description "Двунаправленный буфер")
      (fields (field (name "VOLTAGE") "1V1.. 3.6V  I/Os are 4.6-V Tolerant"))
      (libsource (lib "DDS1") (part "SN74AVC4T774"))
    )
    (comp (ref "U85")
      (value "SN74AVC4T774")
      (footprint "TSSOP-16")
      (description "Двунаправленный буфер")
      (fields (field (name "VOLTAGE") "1V1.. 3.6V  I/Os are 4.6-V Tolerant"))
      (libsource (lib "DDS1") (part "SN74AVC4T774"))
    )
    (comp (ref "U86")
      (value "SN74AVC4T774")
      (footprint "TSSOP-16")
      (description "Двунаправленный буфер")
      (fields (field (name "VOLTAGE") "1V1.. 3.6V  I/Os are 4.6-V Tolerant"))
      (libsource (lib "DDS1") (part "SN74AVC4T774"))
    )
    (comp (ref "U87")
      (value "SN74AVC4T774")
      (footprint "TSSOP-16")
      (description "Двунаправленный буфер")
      (fields (field (name "VOLTAGE") "1V1.. 3.6V  I/Os are 4.6-V Tolerant"))
      (libsource (lib "DDS1") (part "SN74AVC4T774"))
    )
    (comp (ref "U88")
      (value "SN74AVC4T774")
      (footprint "TSSOP-16")
      (description "Двунаправленный буфер")
      (fields (field (name "VOLTAGE") "1V1.. 3.6V  I/Os are 4.6-V Tolerant"))
      (libsource (lib "DDS1") (part "SN74AVC4T774"))
    )
    (comp (ref "U89")
      (value "SN74AVC4T774")
      (footprint "TSSOP-16")
      (description "Двунаправленный буфер")
      (fields (field (name "VOLTAGE") "1V1.. 3.6V  I/Os are 4.6-V Tolerant"))
      (libsource (lib "DDS1") (part "SN74AVC4T774"))
    )
    (comp (ref "U90")
      (value "SN74AVC4T774")
      (footprint "TSSOP-16")
      (description "Двунаправленный буфер")
      (fields (field (name "VOLTAGE") "1V1.. 3.6V  I/Os are 4.6-V Tolerant"))
      (libsource (lib "DDS1") (part "SN74AVC4T774"))
    )
    (comp (ref "U91")
      (value "SN74AVC4T774")
      (footprint "TSSOP-16")
      (description "Двунаправленный буфер")
      (fields (field (name "VOLTAGE") "1V1.. 3.6V  I/Os are 4.6-V Tolerant"))
      (libsource (lib "DDS1") (part "SN74AVC4T774"))
    )
  )
  (nets
    (net (code "3") (name "/+5SL") (class "Default")
      (node (ref "L68") (pin "2") (pinfunction "2_2") (pintype "passive"))
      (node (ref "L76") (pin "2") (pinfunction "2_2") (pintype "passive"))
      (node (ref "L85") (pin "2") (pinfunction "2_2") (pintype "passive"))
      (node (ref "L93") (pin "1") (pinfunction "1_1") (pintype "passive"))
    )
    (net (code "4") (name "/+7SL") (class "Default")
      (node (ref "L71") (pin "2") (pinfunction "2_2") (pintype "passive"))
      (node (ref "L79") (pin "2") (pinfunction "2_2") (pintype "passive"))
      (node (ref "L88") (pin "2") (pinfunction "2_2") (pintype "passive"))
      (node (ref "L96") (pin "2") (pinfunction "2_2") (pintype "passive"))
    )
    (net (code "5") (name "/+12SL") (class "Default")
      (node (ref "L69") (pin "2") (pinfunction "2_2") (pintype "passive"))
      (node (ref "L77") (pin "2") (pinfunction "2_2") (pintype "passive"))
      (node (ref "L86") (pin "2") (pinfunction "2_2") (pintype "passive"))
      (node (ref "L94") (pin "1") (pinfunction "1_1") (pintype "passive"))
    )
    (net (code "6") (name "/+18SL") (class "Default")
      (node (ref "L73") (pin "2") (pinfunction "2_2") (pintype "passive"))
      (node (ref "L82") (pin "2") (pinfunction "2_2") (pintype "passive"))
      (node (ref "L90") (pin "2") (pinfunction "2_2") (pintype "passive"))
      (node (ref "L98") (pin "2") (pinfunction "2_2") (pintype "passive"))
    )
    (net (code "7") (name "/-7SL") (class "Default")
      (node (ref "L70") (pin "2") (pinfunction "2_2") (pintype "passive"))
      (node (ref "L78") (pin "2") (pinfunction "2_2") (pintype "passive"))
      (node (ref "L87") (pin "2") (pinfunction "2_2") (pintype "passive"))
      (node (ref "L95") (pin "2") (pinfunction "2_2") (pintype "passive"))
    )
    (net (code "8") (name "/-18SL") (class "Default")
      (node (ref "L72") (pin "2") (pinfunction "2_2") (pintype "passive"))
      (node (ref "L81") (pin "2") (pinfunction "2_2") (pintype "passive"))
      (node (ref "L89") (pin "2") (pinfunction "2_2") (pintype "passive"))
      (node (ref "L97") (pin "2") (pinfunction "2_2") (pintype "passive"))
    )
    (net (code "9") (name "/3V3SL") (class "Default")
      (node (ref "C185") (pin "2") (pinfunction "2_2") (pintype "passive"))
      (node (ref "C194") (pin "2") (pinfunction "2_2") (pintype "passive"))
      (node (ref "C220") (pin "2") (pinfunction "2_2") (pintype "passive"))
      (node (ref "C221") (pin "2") (pinfunction "2_2") (pintype "passive"))
      (node (ref "C269") (pin "2") (pinfunction "2_2") (pintype "passive"))
      (node (ref "C270") (pin "2") (pinfunction "2_2") (pintype "passive"))
      (node (ref "C271") (pin "2") (pinfunction "2_2") (pintype "passive"))
      (node (ref "C272") (pin "2") (pinfunction "2_2") (pintype "passive"))
      (node (ref "C448") (pin "2") (pinfunction "2_2") (pintype "passive"))
      (node (ref "C449") (pin "2") (pinfunction "2_2") (pintype "passive"))
      (node (ref "C450") (pin "2") (pinfunction "2_2") (pintype "passive"))
      (node (ref "C451") (pin "2") (pinfunction "2_2") (pintype "passive"))
      (node (ref "C452") (pin "2") (pinfunction "2_2") (pintype "passive"))
      (node (ref "C453") (pin "2") (pinfunction "2_2") (pintype "passive"))
      (node (ref "C454") (pin "2") (pinfunction "2_2") (pintype "passive"))
      (node (ref "C455") (pin "2") (pinfunction "2_2") (pintype "passive"))
      (node (ref "C456") (pin "2") (pinfunction "2_2") (pintype "passive"))
      (node (ref "C457") (pin "2") (pinfunction "2_2") (pintype "passive"))
      (node (ref "C458") (pin "2") (pinfunction "2_2") (pintype "passive"))
      (node (ref "C459") (pin "2") (pinfunction "2_2") (pintype "passive"))
      (node (ref "C460") (pin "2") (pinfunction "2_2") (pintype "passive"))
      (node (ref "C461") (pin "2") (pinfunction "2_2") (pintype "passive"))
      (node (ref "C462") (pin "2") (pinfunction "2_2") (pintype "passive"))
      (node (ref "C463") (pin "2") (pinfunction "2_2") (pintype "passive"))
      (node (ref "C464") (pin "2") (pinfunction "2_2") (pintype "passive"))
      (node (ref "C465") (pin "2") (pinfunction "2_2") (pintype "passive"))
      (node (ref "C466") (pin "2") (pinfunction "2_2") (pintype "passive"))
      (node (ref "C467") (pin "2") (pinfunction "2_2") (pintype "passive"))
      (node (ref "C468") (pin "2") (pinfunction "2_2") (pintype "passive"))
      (node (ref "C469") (pin "2") (pinfunction "2_2") (pintype "passive"))
      (node (ref "L54") (pin "2") (pinfunction "2_2") (pintype "passive"))
      (node (ref "L55") (pin "2") (pinfunction "2_2") (pintype "passive"))
      (node (ref "L74") (pin "2") (pinfunction "2_2") (pintype "passive"))
      (node (ref "L75") (pin "2") (pinfunction "2_2") (pintype "passive"))
      (node (ref "L83") (pin "2") (pinfunction "2_2") (pintype "passive"))
      (node (ref "L84") (pin "2") (pinfunction "2_2") (pintype "passive"))
      (node (ref "L91") (pin "2") (pinfunction "2_2") (pintype "passive"))
      (node (ref "L92") (pin "2") (pinfunction "2_2") (pintype "passive"))
      (node (ref "R192") (pin "1") (pinfunction "1_1") (pintype "passive"))
      (node (ref "R207") (pin "1") (pinfunction "1_1") (pintype "passive"))
      (node (ref "R240") (pin "1") (pinfunction "1_1") (pintype "passive"))
      (node (ref "R246") (pin "1") (pinfunction "1_1") (pintype "passive"))
      (node (ref "R354") (pin "1") (pinfunction "1_1") (pintype "passive"))
      (node (ref "R355") (pin "1") (pinfunction "1_1") (pintype "passive"))
      (node (ref "R359") (pin "1") (pinfunction "1_1") (pintype "passive"))
      (node (ref "R360") (pin "1") (pinfunction "1_1") (pintype "passive"))
      (node (ref "R364") (pin "1") (pinfunction "1_1") (pintype "passive"))
      (node (ref "R365") (pin "1") (pinfunction "1_1") (pintype "passive"))
      (node (ref "R369") (pin "1") (pinfunction "1_1") (pintype "passive"))
      (node (ref "R373") (pin "1") (pinfunction "1_1") (pintype "passive"))
      (node (ref "R442") (pin "1") (pinfunction "1_1") (pintype "passive"))
      (node (ref "R444") (pin "1") (pinfunction "1_1") (pintype "passive"))
      (node (ref "R448") (pin "1") (pinfunction "1_1") (pintype "passive"))
      (node (ref "R449") (pin "1") (pinfunction "1_1") (pintype "passive"))
      (node (ref "R459") (pin "1") (pinfunction "1_1") (pintype "passive"))
      (node (ref "R460") (pin "1") (pinfunction "1_1") (pintype "passive"))
      (node (ref "R464") (pin "1") (pinfunction "1_1") (pintype "passive"))
      (node (ref "R465") (pin "1") (pinfunction "1_1") (pintype "passive"))
      (node (ref "R469") (pin "1") (pinfunction "1_1") (pintype "passive"))
      (node (ref "R470") (pin "1") (pinfunction "1_1") (pintype "passive"))
      (node (ref "R474") (pin "1") (pinfunction "1_1") (pintype "passive"))
      (node (ref "R475") (pin "1") (pinfunction "1_1") (pintype "passive"))
      (node (ref "R484") (pin "1") (pinfunction "1_1") (pintype "passive"))
      (node (ref "R485") (pin "1") (pinfunction "1_1") (pintype "passive"))
      (node (ref "R489") (pin "1") (pinfunction "1_1") (pintype "passive"))
      (node (ref "R490") (pin "1") (pinfunction "1_1") (pintype "passive"))
      (node (ref "R494") (pin "1") (pinfunction "1_1") (pintype "passive"))
      (node (ref "R495") (pin "1") (pinfunction "1_1") (pintype "passive"))
      (node (ref "R498") (pin "1") (pinfunction "1_1") (pintype "passive"))
      (node (ref "R499") (pin "1") (pinfunction "1_1") (pintype "passive"))
      (node (ref "R508") (pin "1") (pinfunction "1_1") (pintype "passive"))
      (node (ref "R509") (pin "1") (pinfunction "1_1") (pintype "passive"))
      (node (ref "R513") (pin "1") (pinfunction "1_1") (pintype "passive"))
      (node (ref "R514") (pin "1") (pinfunction "1_1") (pintype "passive"))
      (node (ref "R518") (pin "1") (pinfunction "1_1") (pintype "passive"))
      (node (ref "R519") (pin "1") (pinfunction "1_1") (pintype "passive"))
      (node (ref "R522") (pin "1") (pinfunction "1_1") (pintype "passive"))
      (node (ref "R523") (pin "1") (pinfunction "1_1") (pintype "passive"))
      (node (ref "U39") (pin "15") (pinfunction "Vccb_15") (pintype "passive"))
      (node (ref "U39") (pin "16") (pinfunction "Vcca_16") (pintype "passive"))
      (node (ref "U57") (pin "15") (pinfunction "Vccb_15") (pintype "passive"))
      (node (ref "U57") (pin "16") (pinfunction "Vcca_16") (pintype "passive"))
      (node (ref "U58") (pin "15") (pinfunction "Vccb_15") (pintype "passive"))
      (node (ref "U58") (pin "16") (pinfunction "Vcca_16") (pintype "passive"))
      (node (ref "U80") (pin "15") (pinfunction "Vccb_15") (pintype "passive"))
      (node (ref "U80") (pin "16") (pinfunction "Vcca_16") (pintype "passive"))
      (node (ref "U81") (pin "15") (pinfunction "Vccb_15") (pintype "passive"))
      (node (ref "U81") (pin "16") (pinfunction "Vcca_16") (pintype "passive"))
      (node (ref "U82") (pin "15") (pinfunction "Vccb_15") (pintype "passive"))
      (node (ref "U82") (pin "16") (pinfunction "Vcca_16") (pintype "passive"))
      (node (ref "U83") (pin "15") (pinfunction "Vccb_15") (pintype "passive"))
      (node (ref "U83") (pin "16") (pinfunction "Vcca_16") (pintype "passive"))
      (node (ref "U84") (pin "15") (pinfunction "Vccb_15") (pintype "passive"))
      (node (ref "U84") (pin "16") (pinfunction "Vcca_16") (pintype "passive"))
      (node (ref "U85") (pin "15") (pinfunction "Vccb_15") (pintype "passive"))
      (node (ref "U85") (pin "16") (pinfunction "Vcca_16") (pintype "passive"))
      (node (ref "U86") (pin "15") (pinfunction "Vccb_15") (pintype "passive"))
      (node (ref "U86") (pin "16") (pinfunction "Vcca_16") (pintype "passive"))
      (node (ref "U87") (pin "15") (pinfunction "Vccb_15") (pintype "passive"))
      (node (ref "U87") (pin "16") (pinfunction "Vcca_16") (pintype "passive"))
      (node (ref "U88") (pin "15") (pinfunction "Vccb_15") (pintype "passive"))
      (node (ref "U88") (pin "16") (pinfunction "Vcca_16") (pintype "passive"))
      (node (ref "U89") (pin "15") (pinfunction "Vccb_15") (pintype "passive"))
      (node (ref "U89") (pin "16") (pinfunction "Vcca_16") (pintype "passive"))
      (node (ref "U90") (pin "15") (pinfunction "Vccb_15") (pintype "passive"))
      (node (ref "U90") (pin "16") (pinfunction "Vcca_16") (pintype "passive"))
      (node (ref "U91") (pin "15") (pinfunction "Vccb_15") (pintype "passive"))
      (node (ref "U91") (pin "16") (pinfunction "Vcca_16") (pintype "passive"))
    )
    (net (code "11") (name "/IO_Slow1") (class "Default")
      (node (ref "R153") (pin "2") (pinfunction "2_2") (pintype "passive"))
    )
    (net (code "12") (name "/IO_Slow2") (class "Default")
      (node (ref "R209") (pin "2") (pinfunction "2_2") (pintype "passive"))
    )
    (net (code "13") (name "/IO_Slow3") (class "Default")
      (node (ref "R256") (pin "2") (pinfunction "2_2") (pintype "passive"))
    )
    (net (code "14") (name "/IO_Slow4") (class "Default")
      (node (ref "R445") (pin "2") (pinfunction "2_2") (pintype "passive"))
    )
    (net (code "15") (name "/IO_Slow5") (class "Default")
      (node (ref "R182") (pin "2") (pinfunction "2_2") (pintype "passive"))
    )
    (net (code "16") (name "/IO_Slow6") (class "Default")
      (node (ref "R220") (pin "2") (pinfunction "2_2") (pintype "passive"))
    )
    (net (code "17") (name "/IO_Slow7") (class "Default")
      (node (ref "R437") (pin "2") (pinfunction "2_2") (pintype "passive"))
    )
    (net (code "18") (name "/IO_Slow8") (class "Default")
      (node (ref "R446") (pin "2") (pinfunction "2_2") (pintype "passive"))
    )
    (net (code "19") (name "/IO_Slow9") (class "Default")
      (node (ref "R183") (pin "2") (pinfunction "2_2") (pintype "passive"))
    )
    (net (code "20") (name "/IO_Slow10") (class "Default")
      (node (ref "R238") (pin "2") (pinfunction "2_2") (pintype "passive"))
    )
    (net (code "21") (name "/IO_Slow11") (class "Default")
      (node (ref "R438") (pin "2") (pinfunction "2_2") (pintype "passive"))
    )
    (net (code "22") (name "/IO_Slow12") (class "Default")
      (node (ref "R447") (pin "2") (pinfunction "2_2") (pintype "passive"))
    )
    (net (code "23") (name "/IO_Slow13") (class "Default")
      (node (ref "R456") (pin "2") (pinfunction "2_2") (pintype "passive"))
    )
    (net (code "24") (name "/IO_Slow14") (class "Default")
      (node (ref "R461") (pin "2") (pinfunction "2_2") (pintype "passive"))
    )
    (net (code "25") (name "/IO_Slow15") (class "Default")
      (node (ref "R466") (pin "2") (pinfunction "2_2") (pintype "passive"))
    )
    (net (code "26") (name "/IO_Slow16") (class "Default")
      (node (ref "R471") (pin "2") (pinfunction "2_2") (pintype "passive"))
    )
    (net (code "27") (name "/IO_Slow17") (class "Default")
      (node (ref "R457") (pin "2") (pinfunction "2_2") (pintype "passive"))
    )
    (net (code "28") (name "/IO_Slow18") (class "Default")
      (node (ref "R462") (pin "1") (pinfunction "1_1") (pintype "passive"))
    )
    (net (code "29") (name "/IO_Slow19") (class "Default")
      (node (ref "R467") (pin "2") (pinfunction "2_2") (pintype "passive"))
    )
    (net (code "30") (name "/IO_Slow20") (class "Default")
      (node (ref "R472") (pin "2") (pinfunction "2_2") (pintype "passive"))
    )
    (net (code "31") (name "/IO_Slow21") (class "Default")
      (node (ref "R458") (pin "2") (pinfunction "2_2") (pintype "passive"))
    )
    (net (code "32") (name "/IO_Slow22") (class "Default")
      (node (ref "R463") (pin "2") (pinfunction "2_2") (pintype "passive"))
    )
    (net (code "33") (name "/IO_Slow23") (class "Default")
      (node (ref "R468") (pin "2") (pinfunction "2_2") (pintype "passive"))
    )
    (net (code "34") (name "/IO_Slow24") (class "Default")
      (node (ref "R473") (pin "2") (pinfunction "2_2") (pintype "passive"))
    )
    (net (code "35") (name "/IO_Slow25") (class "Default")
      (node (ref "R480") (pin "2") (pinfunction "2_2") (pintype "passive"))
    )
    (net (code "36") (name "/IO_Slow26") (class "Default")
      (node (ref "R483") (pin "2") (pinfunction "2_2") (pintype "passive"))
    )
    (net (code "37") (name "/IO_Slow27") (class "Default")
      (node (ref "R488") (pin "2") (pinfunction "2_2") (pintype "passive"))
    )
    (net (code "38") (name "/IO_Slow28") (class "Default")
      (node (ref "R493") (pin "2") (pinfunction "2_2") (pintype "passive"))
    )
    (net (code "39") (name "/IO_Slow29") (class "Default")
      (node (ref "R481") (pin "2") (pinfunction "2_2") (pintype "passive"))
    )
    (net (code "40") (name "/IO_Slow30") (class "Default")
      (node (ref "R486") (pin "2") (pinfunction "2_2") (pintype "passive"))
    )
    (net (code "41") (name "/IO_Slow31") (class "Default")
      (node (ref "R491") (pin "2") (pinfunction "2_2") (pintype "passive"))
    )
    (net (code "42") (name "/IO_Slow32") (class "Default")
      (node (ref "R496") (pin "2") (pinfunction "2_2") (pintype "passive"))
    )
    (net (code "43") (name "/IO_Slow33") (class "Default")
      (node (ref "R482") (pin "2") (pinfunction "2_2") (pintype "passive"))
    )
    (net (code "44") (name "/IO_Slow34") (class "Default")
      (node (ref "R487") (pin "2") (pinfunction "2_2") (pintype "passive"))
    )
    (net (code "45") (name "/IO_Slow35") (class "Default")
      (node (ref "R492") (pin "2") (pinfunction "2_2") (pintype "passive"))
    )
    (net (code "46") (name "/IO_Slow36") (class "Default")
      (node (ref "R497") (pin "2") (pinfunction "2_2") (pintype "passive"))
    )
    (net (code "47") (name "/IO_Slow37") (class "Default")
      (node (ref "R504") (pin "2") (pinfunction "2_2") (pintype "passive"))
    )
    (net (code "48") (name "/IO_Slow38") (class "Default")
      (node (ref "R505") (pin "2") (pinfunction "2_2") (pintype "passive"))
    )
    (net (code "49") (name "/IO_Slow39") (class "Default")
      (node (ref "R510") (pin "2") (pinfunction "2_2") (pintype "passive"))
    )
    (net (code "50") (name "/IO_Slow40") (class "Default")
      (node (ref "R515") (pin "2") (pinfunction "2_2") (pintype "passive"))
    )
    (net (code "51") (name "/IO_Slow41") (class "Default")
      (node (ref "R506") (pin "2") (pinfunction "2_2") (pintype "passive"))
    )
    (net (code "52") (name "/IO_Slow42") (class "Default")
      (node (ref "R511") (pin "2") (pinfunction "2_2") (pintype "passive"))
    )
    (net (code "53") (name "/IO_Slow43") (class "Default")
      (node (ref "R516") (pin "2") (pinfunction "2_2") (pintype "passive"))
    )
    (net (code "54") (name "/IO_Slow44") (class "Default")
      (node (ref "R520") (pin "2") (pinfunction "2_2") (pintype "passive"))
    )
    (net (code "55") (name "/IO_Slow45") (class "Default")
      (node (ref "R507") (pin "2") (pinfunction "2_2") (pintype "passive"))
    )
    (net (code "56") (name "/IO_Slow46") (class "Default")
      (node (ref "R512") (pin "2") (pinfunction "2_2") (pintype "passive"))
    )
    (net (code "57") (name "/IO_Slow47") (class "Default")
      (node (ref "R517") (pin "2") (pinfunction "2_2") (pintype "passive"))
    )
    (net (code "58") (name "/IO_Slow48") (class "Default")
      (node (ref "R521") (pin "2") (pinfunction "2_2") (pintype "passive"))
    )
    (net (code "59") (name "/IO_Slow49") (class "Default")
      (node (ref "R351") (pin "2") (pinfunction "2_2") (pintype "passive"))
    )
    (net (code "60") (name "/IO_Slow50") (class "Default")
      (node (ref "R356") (pin "2") (pinfunction "2_2") (pintype "passive"))
    )
    (net (code "61") (name "/IO_Slow51") (class "Default")
      (node (ref "R361") (pin "2") (pinfunction "2_2") (pintype "passive"))
    )
    (net (code "62") (name "/IO_Slow52") (class "Default")
      (node (ref "R366") (pin "2") (pinfunction "2_2") (pintype "passive"))
    )
    (net (code "63") (name "/IO_Slow53") (class "Default")
      (node (ref "R352") (pin "2") (pinfunction "2_2") (pintype "passive"))
    )
    (net (code "64") (name "/IO_Slow54") (class "Default")
      (node (ref "R357") (pin "2") (pinfunction "2_2") (pintype "passive"))
    )
    (net (code "65") (name "/IO_Slow55") (class "Default")
      (node (ref "R362") (pin "2") (pinfunction "2_2") (pintype "passive"))
    )
    (net (code "66") (name "/IO_Slow56") (class "Default")
      (node (ref "R367") (pin "2") (pinfunction "2_2") (pintype "passive"))
    )
    (net (code "67") (name "/IO_Slow57") (class "Default")
      (node (ref "R353") (pin "2") (pinfunction "2_2") (pintype "passive"))
    )
    (net (code "68") (name "/IO_Slow58") (class "Default")
      (node (ref "R358") (pin "2") (pinfunction "2_2") (pintype "passive"))
    )
    (net (code "69") (name "/IO_Slow59") (class "Default")
      (node (ref "R363") (pin "2") (pinfunction "2_2") (pintype "passive"))
    )
    (net (code "70") (name "/IO_Slow60") (class "Default")
      (node (ref "R368") (pin "2") (pinfunction "2_2") (pintype "passive"))
    )
    (net (code "74") (name "/in1") (class "Default")
      (node (ref "J42") (pin "4") (pinfunction "I/O_4") (pintype "bidirectional"))
      (node (ref "U81") (pin "3") (pinfunction "A1_3") (pintype "passive"))
    )
    (net (code "75") (name "/in2") (class "Default")
      (node (ref "J42") (pin "8") (pinfunction "I/O_8") (pintype "bidirectional"))
      (node (ref "U81") (pin "4") (pinfunction "A2_4") (pintype "passive"))
    )
    (net (code "76") (name "/in3") (class "Default")
      (node (ref "J42") (pin "12") (pinfunction "I/O_12") (pintype "bidirectional"))
      (node (ref "U81") (pin "5") (pinfunction "A3_5") (pintype "passive"))
    )
    (net (code "77") (name "/in4") (class "Default")
      (node (ref "J42") (pin "16") (pinfunction "I/O_16") (pintype "bidirectional"))
      (node (ref "U81") (pin "6") (pinfunction "A4_6") (pintype "passive"))
    )
    (net (code "78") (name "/in5") (class "Default")
      (node (ref "J43") (pin "4") (pinfunction "I/O_4") (pintype "bidirectional"))
      (node (ref "U84") (pin "3") (pinfunction "A1_3") (pintype "passive"))
    )
    (net (code "79") (name "/in6") (class "Default")
      (node (ref "J43") (pin "8") (pinfunction "I/O_8") (pintype "bidirectional"))
      (node (ref "U84") (pin "4") (pinfunction "A2_4") (pintype "passive"))
    )
    (net (code "80") (name "/in7") (class "Default")
      (node (ref "J43") (pin "12") (pinfunction "I/O_12") (pintype "bidirectional"))
      (node (ref "U84") (pin "5") (pinfunction "A3_5") (pintype "passive"))
    )
    (net (code "81") (name "/in8") (class "Default")
      (node (ref "J43") (pin "16") (pinfunction "I/O_16") (pintype "bidirectional"))
      (node (ref "U84") (pin "6") (pinfunction "A4_6") (pintype "passive"))
    )
    (net (code "82") (name "/in9") (class "Default")
      (node (ref "J44") (pin "4") (pinfunction "I/O_4") (pintype "bidirectional"))
      (node (ref "U87") (pin "3") (pinfunction "A1_3") (pintype "passive"))
    )
    (net (code "83") (name "/in10") (class "Default")
      (node (ref "J44") (pin "8") (pinfunction "I/O_8") (pintype "bidirectional"))
      (node (ref "U87") (pin "4") (pinfunction "A2_4") (pintype "passive"))
    )
    (net (code "84") (name "/in11") (class "Default")
      (node (ref "J44") (pin "12") (pinfunction "I/O_12") (pintype "bidirectional"))
      (node (ref "U87") (pin "5") (pinfunction "A3_5") (pintype "passive"))
    )
    (net (code "85") (name "/in12") (class "Default")
      (node (ref "J44") (pin "16") (pinfunction "I/O_16") (pintype "bidirectional"))
      (node (ref "U87") (pin "6") (pinfunction "A4_6") (pintype "passive"))
    )
    (net (code "86") (name "/in13") (class "Default")
      (node (ref "J45") (pin "4") (pinfunction "I/O_4") (pintype "bidirectional"))
      (node (ref "U90") (pin "3") (pinfunction "A1_3") (pintype "passive"))
    )
    (net (code "87") (name "/in14") (class "Default")
      (node (ref "J45") (pin "8") (pinfunction "I/O_8") (pintype "bidirectional"))
      (node (ref "U90") (pin "4") (pinfunction "A2_4") (pintype "passive"))
    )
    (net (code "88") (name "/in15") (class "Default")
      (node (ref "J45") (pin "12") (pinfunction "I/O_12") (pintype "bidirectional"))
      (node (ref "U90") (pin "5") (pinfunction "A3_5") (pintype "passive"))
    )
    (net (code "89") (name "/in16") (class "Default")
      (node (ref "J45") (pin "16") (pinfunction "I/O_16") (pintype "bidirectional"))
      (node (ref "U90") (pin "6") (pinfunction "A4_6") (pintype "passive"))
    )
    (net (code "90") (name "/in17") (class "Default")
      (node (ref "J42") (pin "20") (pinfunction "I/O_20") (pintype "bidirectional"))
      (node (ref "J43") (pin "20") (pinfunction "I/O_20") (pintype "bidirectional"))
      (node (ref "J44") (pin "20") (pinfunction "I/O_20") (pintype "bidirectional"))
      (node (ref "J45") (pin "20") (pinfunction "I/O_20") (pintype "bidirectional"))
      (node (ref "U57") (pin "6") (pinfunction "A4_6") (pintype "passive"))
    )
    (net (code "91") (name "/in18") (class "Default")
      (node (ref "J42") (pin "24") (pinfunction "I/O_24") (pintype "bidirectional"))
      (node (ref "J43") (pin "24") (pinfunction "I/O_24") (pintype "bidirectional"))
      (node (ref "J44") (pin "24") (pinfunction "I/O_24") (pintype "bidirectional"))
      (node (ref "J45") (pin "24") (pinfunction "I/O_24") (pintype "bidirectional"))
      (node (ref "U57") (pin "5") (pinfunction "A3_5") (pintype "passive"))
    )
    (net (code "92") (name "/in19") (class "Default")
      (node (ref "J42") (pin "28") (pinfunction "I/O_28") (pintype "bidirectional"))
      (node (ref "J43") (pin "28") (pinfunction "I/O_28") (pintype "bidirectional"))
      (node (ref "J44") (pin "28") (pinfunction "I/O_28") (pintype "bidirectional"))
      (node (ref "J45") (pin "28") (pinfunction "I/O_28") (pintype "bidirectional"))
      (node (ref "U57") (pin "4") (pinfunction "A2_4") (pintype "passive"))
    )
    (net (code "93") (name "/in20") (class "Default")
      (node (ref "J42") (pin "32") (pinfunction "I/O_32") (pintype "bidirectional"))
      (node (ref "J43") (pin "32") (pinfunction "I/O_32") (pintype "bidirectional"))
      (node (ref "J44") (pin "32") (pinfunction "I/O_32") (pintype "bidirectional"))
      (node (ref "J45") (pin "32") (pinfunction "I/O_32") (pintype "bidirectional"))
      (node (ref "U57") (pin "3") (pinfunction "A1_3") (pintype "passive"))
    )
    (net (code "94") (name "/inOut1") (class "Default")
      (node (ref "J42") (pin "33") (pinfunction "I/O_33") (pintype "bidirectional"))
      (node (ref "U82") (pin "6") (pinfunction "A4_6") (pintype "passive"))
    )
    (net (code "95") (name "/inOut2") (class "Default")
      (node (ref "J42") (pin "37") (pinfunction "I/O_37") (pintype "bidirectional"))
      (node (ref "U82") (pin "5") (pinfunction "A3_5") (pintype "passive"))
    )
    (net (code "96") (name "/inOut3") (class "Default")
      (node (ref "J42") (pin "41") (pinfunction "I/O_41") (pintype "bidirectional"))
      (node (ref "U82") (pin "4") (pinfunction "A2_4") (pintype "passive"))
    )
    (net (code "97") (name "/inOut4") (class "Default")
      (node (ref "J42") (pin "45") (pinfunction "I/O_45") (pintype "bidirectional"))
      (node (ref "U82") (pin "3") (pinfunction "A1_3") (pintype "passive"))
    )
    (net (code "98") (name "/inOut5") (class "Default")
      (node (ref "J43") (pin "33") (pinfunction "I/O_33") (pintype "bidirectional"))
      (node (ref "U85") (pin "6") (pinfunction "A4_6") (pintype "passive"))
    )
    (net (code "99") (name "/inOut6") (class "Default")
      (node (ref "J43") (pin "37") (pinfunction "I/O_37") (pintype "bidirectional"))
      (node (ref "U85") (pin "5") (pinfunction "A3_5") (pintype "passive"))
    )
    (net (code "100") (name "/inOut7") (class "Default")
      (node (ref "J43") (pin "41") (pinfunction "I/O_41") (pintype "bidirectional"))
      (node (ref "U85") (pin "4") (pinfunction "A2_4") (pintype "passive"))
    )
    (net (code "101") (name "/inOut8") (class "Default")
      (node (ref "J43") (pin "45") (pinfunction "I/O_45") (pintype "bidirectional"))
      (node (ref "U85") (pin "3") (pinfunction "A1_3") (pintype "passive"))
    )
    (net (code "102") (name "/inOut9") (class "Default")
      (node (ref "J44") (pin "33") (pinfunction "I/O_33") (pintype "bidirectional"))
      (node (ref "U88") (pin "6") (pinfunction "A4_6") (pintype "passive"))
    )
    (net (code "103") (name "/inOut10") (class "Default")
      (node (ref "J44") (pin "37") (pinfunction "I/O_37") (pintype "bidirectional"))
      (node (ref "U88") (pin "5") (pinfunction "A3_5") (pintype "passive"))
    )
    (net (code "104") (name "/inOut11") (class "Default")
      (node (ref "J44") (pin "41") (pinfunction "I/O_41") (pintype "bidirectional"))
      (node (ref "U88") (pin "4") (pinfunction "A2_4") (pintype "passive"))
    )
    (net (code "105") (name "/inOut12") (class "Default")
      (node (ref "J44") (pin "45") (pinfunction "I/O_45") (pintype "bidirectional"))
      (node (ref "U88") (pin "3") (pinfunction "A1_3") (pintype "passive"))
    )
    (net (code "106") (name "/inOut13") (class "Default")
      (node (ref "J45") (pin "33") (pinfunction "I/O_33") (pintype "bidirectional"))
      (node (ref "U91") (pin "6") (pinfunction "A4_6") (pintype "passive"))
    )
    (net (code "107") (name "/inOut14") (class "Default")
      (node (ref "J45") (pin "37") (pinfunction "I/O_37") (pintype "bidirectional"))
      (node (ref "U91") (pin "5") (pinfunction "A3_5") (pintype "passive"))
    )
    (net (code "108") (name "/inOut15") (class "Default")
      (node (ref "J45") (pin "41") (pinfunction "I/O_41") (pintype "bidirectional"))
      (node (ref "U91") (pin "4") (pinfunction "A2_4") (pintype "passive"))
    )
    (net (code "109") (name "/inOut16") (class "Default")
      (node (ref "J45") (pin "45") (pinfunction "I/O_45") (pintype "bidirectional"))
      (node (ref "U91") (pin "3") (pinfunction "A1_3") (pintype "passive"))
    )
    (net (code "110") (name "/inOut17") (class "Default")
      (node (ref "J42") (pin "49") (pinfunction "I/O_49") (pintype "bidirectional"))
      (node (ref "J43") (pin "49") (pinfunction "I/O_49") (pintype "bidirectional"))
      (node (ref "J44") (pin "49") (pinfunction "I/O_49") (pintype "bidirectional"))
      (node (ref "J45") (pin "17") (pinfunction "I/O_17") (pintype "bidirectional"))
      (node (ref "J45") (pin "49") (pinfunction "I/O_49") (pintype "bidirectional"))
      (node (ref "U58") (pin "6") (pinfunction "A4_6") (pintype "passive"))
    )
    (net (code "111") (name "/inOut18") (class "Default")
      (node (ref "J42") (pin "53") (pinfunction "I/O_53") (pintype "bidirectional"))
      (node (ref "J43") (pin "53") (pinfunction "I/O_53") (pintype "bidirectional"))
      (node (ref "J44") (pin "53") (pinfunction "I/O_53") (pintype "bidirectional"))
      (node (ref "J45") (pin "21") (pinfunction "I/O_21") (pintype "bidirectional"))
      (node (ref "J45") (pin "53") (pinfunction "I/O_53") (pintype "bidirectional"))
      (node (ref "U58") (pin "5") (pinfunction "A3_5") (pintype "passive"))
    )
    (net (code "112") (name "/inOut19") (class "Default")
      (node (ref "J42") (pin "57") (pinfunction "I/O_57") (pintype "bidirectional"))
      (node (ref "J43") (pin "57") (pinfunction "I/O_57") (pintype "bidirectional"))
      (node (ref "J44") (pin "57") (pinfunction "I/O_57") (pintype "bidirectional"))
      (node (ref "J45") (pin "25") (pinfunction "I/O_25") (pintype "bidirectional"))
      (node (ref "J45") (pin "57") (pinfunction "I/O_57") (pintype "bidirectional"))
      (node (ref "U58") (pin "4") (pinfunction "A2_4") (pintype "passive"))
    )
    (net (code "113") (name "/inOut20") (class "Default")
      (node (ref "J42") (pin "61") (pinfunction "I/O_61") (pintype "bidirectional"))
      (node (ref "J43") (pin "61") (pinfunction "I/O_61") (pintype "bidirectional"))
      (node (ref "J44") (pin "61") (pinfunction "I/O_61") (pintype "bidirectional"))
      (node (ref "J45") (pin "29") (pinfunction "I/O_29") (pintype "bidirectional"))
      (node (ref "J45") (pin "61") (pinfunction "I/O_61") (pintype "bidirectional"))
      (node (ref "U58") (pin "3") (pinfunction "A1_3") (pintype "passive"))
    )
    (net (code "114") (name "/out1") (class "Default")
      (node (ref "J42") (pin "1") (pinfunction "I/O_1") (pintype "bidirectional"))
      (node (ref "U80") (pin "6") (pinfunction "A4_6") (pintype "passive"))
    )
    (net (code "115") (name "/out2") (class "Default")
      (node (ref "J42") (pin "5") (pinfunction "I/O_5") (pintype "bidirectional"))
      (node (ref "U80") (pin "5") (pinfunction "A3_5") (pintype "passive"))
    )
    (net (code "116") (name "/out3") (class "Default")
      (node (ref "J42") (pin "9") (pinfunction "I/O_9") (pintype "bidirectional"))
      (node (ref "U80") (pin "4") (pinfunction "A2_4") (pintype "passive"))
    )
    (net (code "117") (name "/out4") (class "Default")
      (node (ref "J42") (pin "13") (pinfunction "I/O_13") (pintype "bidirectional"))
      (node (ref "U80") (pin "3") (pinfunction "A1_3") (pintype "passive"))
    )
    (net (code "118") (name "/out5") (class "Default")
      (node (ref "J43") (pin "1") (pinfunction "I/O_1") (pintype "bidirectional"))
      (node (ref "U83") (pin "6") (pinfunction "A4_6") (pintype "passive"))
    )
    (net (code "119") (name "/out6") (class "Default")
      (node (ref "J43") (pin "5") (pinfunction "I/O_5") (pintype "bidirectional"))
      (node (ref "U83") (pin "5") (pinfunction "A3_5") (pintype "passive"))
    )
    (net (code "120") (name "/out7") (class "Default")
      (node (ref "J43") (pin "9") (pinfunction "I/O_9") (pintype "bidirectional"))
      (node (ref "U83") (pin "4") (pinfunction "A2_4") (pintype "passive"))
    )
    (net (code "121") (name "/out8") (class "Default")
      (node (ref "J43") (pin "13") (pinfunction "I/O_13") (pintype "bidirectional"))
      (node (ref "U83") (pin "3") (pinfunction "A1_3") (pintype "passive"))
    )
    (net (code "122") (name "/out9") (class "Default")
      (node (ref "J44") (pin "1") (pinfunction "I/O_1") (pintype "bidirectional"))
      (node (ref "U86") (pin "6") (pinfunction "A4_6") (pintype "passive"))
    )
    (net (code "123") (name "/out10") (class "Default")
      (node (ref "J44") (pin "5") (pinfunction "I/O_5") (pintype "bidirectional"))
      (node (ref "U86") (pin "5") (pinfunction "A3_5") (pintype "passive"))
    )
    (net (code "124") (name "/out11") (class "Default")
      (node (ref "J44") (pin "9") (pinfunction "I/O_9") (pintype "bidirectional"))
      (node (ref "U86") (pin "4") (pinfunction "A2_4") (pintype "passive"))
    )
    (net (code "125") (name "/out12") (class "Default")
      (node (ref "J44") (pin "13") (pinfunction "I/O_13") (pintype "bidirectional"))
      (node (ref "U86") (pin "3") (pinfunction "A1_3") (pintype "passive"))
    )
    (net (code "126") (name "/out13") (class "Default")
      (node (ref "J45") (pin "1") (pinfunction "I/O_1") (pintype "bidirectional"))
      (node (ref "U89") (pin "6") (pinfunction "A4_6") (pintype "passive"))
    )
    (net (code "127") (name "/out14") (class "Default")
      (node (ref "J45") (pin "5") (pinfunction "I/O_5") (pintype "bidirectional"))
      (node (ref "U89") (pin "5") (pinfunction "A3_5") (pintype "passive"))
    )
    (net (code "128") (name "/out15") (class "Default")
      (node (ref "J45") (pin "9") (pinfunction "I/O_9") (pintype "bidirectional"))
      (node (ref "U89") (pin "4") (pinfunction "A2_4") (pintype "passive"))
    )
    (net (code "129") (name "/out16") (class "Default")
      (node (ref "J45") (pin "13") (pinfunction "I/O_13") (pintype "bidirectional"))
      (node (ref "U89") (pin "3") (pinfunction "A1_3") (pintype "passive"))
    )
    (net (code "130") (name "/out17") (class "Default")
      (node (ref "J42") (pin "17") (pinfunction "I/O_17") (pintype "bidirectional"))
      (node (ref "J43") (pin "17") (pinfunction "I/O_17") (pintype "bidirectional"))
      (node (ref "J44") (pin "17") (pinfunction "I/O_17") (pintype "bidirectional"))
      (node (ref "U39") (pin "3") (pinfunction "A1_3") (pintype "passive"))
    )
    (net (code "131") (name "/out18") (class "Default")
      (node (ref "J42") (pin "21") (pinfunction "I/O_21") (pintype "bidirectional"))
      (node (ref "J43") (pin "21") (pinfunction "I/O_21") (pintype "bidirectional"))
      (node (ref "J44") (pin "21") (pinfunction "I/O_21") (pintype "bidirectional"))
      (node (ref "U39") (pin "4") (pinfunction "A2_4") (pintype "passive"))
    )
    (net (code "132") (name "/out19") (class "Default")
      (node (ref "J42") (pin "25") (pinfunction "I/O_25") (pintype "bidirectional"))
      (node (ref "J43") (pin "25") (pinfunction "I/O_25") (pintype "bidirectional"))
      (node (ref "J44") (pin "25") (pinfunction "I/O_25") (pintype "bidirectional"))
      (node (ref "U39") (pin "5") (pinfunction "A3_5") (pintype "passive"))
    )
    (net (code "133") (name "/out20") (class "Default")
      (node (ref "J42") (pin "29") (pinfunction "I/O_29") (pintype "bidirectional"))
      (node (ref "J43") (pin "29") (pinfunction "I/O_29") (pintype "bidirectional"))
      (node (ref "J44") (pin "29") (pinfunction "I/O_29") (pintype "bidirectional"))
      (node (ref "U39") (pin "6") (pinfunction "A4_6") (pintype "passive"))
    )
    (net (code "135") (name "GND") (class "Default")
      (node (ref "C185") (pin "1") (pinfunction "1_1") (pintype "passive"))
      (node (ref "C194") (pin "1") (pinfunction "1_1") (pintype "passive"))
      (node (ref "C220") (pin "1") (pinfunction "1_1") (pintype "passive"))
      (node (ref "C221") (pin "1") (pinfunction "1_1") (pintype "passive"))
      (node (ref "C269") (pin "1") (pinfunction "1_1") (pintype "passive"))
      (node (ref "C270") (pin "1") (pinfunction "1_1") (pintype "passive"))
      (node (ref "C271") (pin "1") (pinfunction "1_1") (pintype "passive"))
      (node (ref "C272") (pin "1") (pinfunction "1_1") (pintype "passive"))
      (node (ref "C448") (pin "1") (pinfunction "1_1") (pintype "passive"))
      (node (ref "C449") (pin "1") (pinfunction "1_1") (pintype "passive"))
      (node (ref "C450") (pin "1") (pinfunction "1_1") (pintype "passive"))
      (node (ref "C451") (pin "1") (pinfunction "1_1") (pintype "passive"))
      (node (ref "C452") (pin "1") (pinfunction "1_1") (pintype "passive"))
      (node (ref "C453") (pin "1") (pinfunction "1_1") (pintype "passive"))
      (node (ref "C454") (pin "1") (pinfunction "1_1") (pintype "passive"))
      (node (ref "C455") (pin "1") (pinfunction "1_1") (pintype "passive"))
      (node (ref "C456") (pin "1") (pinfunction "1_1") (pintype "passive"))
      (node (ref "C457") (pin "1") (pinfunction "1_1") (pintype "passive"))
      (node (ref "C458") (pin "1") (pinfunction "1_1") (pintype "passive"))
      (node (ref "C459") (pin "1") (pinfunction "1_1") (pintype "passive"))
      (node (ref "C460") (pin "1") (pinfunction "1_1") (pintype "passive"))
      (node (ref "C461") (pin "1") (pinfunction "1_1") (pintype "passive"))
      (node (ref "C462") (pin "1") (pinfunction "1_1") (pintype "passive"))
      (node (ref "C463") (pin "1") (pinfunction "1_1") (pintype "passive"))
      (node (ref "C464") (pin "1") (pinfunction "1_1") (pintype "passive"))
      (node (ref "C465") (pin "1") (pinfunction "1_1") (pintype "passive"))
      (node (ref "C466") (pin "1") (pinfunction "1_1") (pintype "passive"))
      (node (ref "C467") (pin "1") (pinfunction "1_1") (pintype "passive"))
      (node (ref "C468") (pin "1") (pinfunction "1_1") (pintype "passive"))
      (node (ref "C469") (pin "1") (pinfunction "1_1") (pintype "passive"))
      (node (ref "J42") (pin "10") (pinfunction "I/O_10") (pintype "bidirectional"))
      (node (ref "J42") (pin "11") (pinfunction "I/O_11") (pintype "bidirectional"))
      (node (ref "J42") (pin "14") (pinfunction "I/O_14") (pintype "bidirectional"))
      (node (ref "J42") (pin "15") (pinfunction "I/O_15") (pintype "bidirectional"))
      (node (ref "J42") (pin "18") (pinfunction "I/O_18") (pintype "bidirectional"))
      (node (ref "J42") (pin "19") (pinfunction "I/O_19") (pintype "bidirectional"))
      (node (ref "J42") (pin "2") (pinfunction "I/O_2") (pintype "bidirectional"))
      (node (ref "J42") (pin "22") (pinfunction "I/O_22") (pintype "bidirectional"))
      (node (ref "J42") (pin "23") (pinfunction "I/O_23") (pintype "bidirectional"))
      (node (ref "J42") (pin "26") (pinfunction "I/O_26") (pintype "bidirectional"))
      (node (ref "J42") (pin "27") (pinfunction "I/O_27") (pintype "bidirectional"))
      (node (ref "J42") (pin "3") (pinfunction "I/O_3") (pintype "bidirectional"))
      (node (ref "J42") (pin "30") (pinfunction "I/O_30") (pintype "bidirectional"))
      (node (ref "J42") (pin "31") (pinfunction "I/O_31") (pintype "bidirectional"))
      (node (ref "J42") (pin "34") (pinfunction "I/O_34") (pintype "bidirectional"))
      (node (ref "J42") (pin "35") (pinfunction "I/O_35") (pintype "bidirectional"))
      (node (ref "J42") (pin "38") (pinfunction "I/O_38") (pintype "bidirectional"))
      (node (ref "J42") (pin "39") (pinfunction "I/O_39") (pintype "bidirectional"))
      (node (ref "J42") (pin "42") (pinfunction "I/O_42") (pintype "bidirectional"))
      (node (ref "J42") (pin "43") (pinfunction "I/O_43") (pintype "bidirectional"))
      (node (ref "J42") (pin "46") (pinfunction "I/O_46") (pintype "bidirectional"))
      (node (ref "J42") (pin "47") (pinfunction "I/O_47") (pintype "bidirectional"))
      (node (ref "J42") (pin "50") (pinfunction "I/O_50") (pintype "bidirectional"))
      (node (ref "J42") (pin "51") (pinfunction "I/O_51") (pintype "bidirectional"))
      (node (ref "J42") (pin "54") (pinfunction "I/O_54") (pintype "bidirectional"))
      (node (ref "J42") (pin "55") (pinfunction "I/O_55") (pintype "bidirectional"))
      (node (ref "J42") (pin "58") (pinfunction "I/O_58") (pintype "bidirectional"))
      (node (ref "J42") (pin "59") (pinfunction "I/O_59") (pintype "bidirectional"))
      (node (ref "J42") (pin "6") (pinfunction "I/O_6") (pintype "bidirectional"))
      (node (ref "J42") (pin "62") (pinfunction "I/O_62") (pintype "bidirectional"))
      (node (ref "J42") (pin "63") (pinfunction "I/O_63") (pintype "bidirectional"))
      (node (ref "J42") (pin "7") (pinfunction "I/O_7") (pintype "bidirectional"))
      (node (ref "J43") (pin "10") (pinfunction "I/O_10") (pintype "bidirectional"))
      (node (ref "J43") (pin "11") (pinfunction "I/O_11") (pintype "bidirectional"))
      (node (ref "J43") (pin "14") (pinfunction "I/O_14") (pintype "bidirectional"))
      (node (ref "J43") (pin "15") (pinfunction "I/O_15") (pintype "bidirectional"))
      (node (ref "J43") (pin "18") (pinfunction "I/O_18") (pintype "bidirectional"))
      (node (ref "J43") (pin "19") (pinfunction "I/O_19") (pintype "bidirectional"))
      (node (ref "J43") (pin "2") (pinfunction "I/O_2") (pintype "bidirectional"))
      (node (ref "J43") (pin "22") (pinfunction "I/O_22") (pintype "bidirectional"))
      (node (ref "J43") (pin "23") (pinfunction "I/O_23") (pintype "bidirectional"))
      (node (ref "J43") (pin "26") (pinfunction "I/O_26") (pintype "bidirectional"))
      (node (ref "J43") (pin "27") (pinfunction "I/O_27") (pintype "bidirectional"))
      (node (ref "J43") (pin "3") (pinfunction "I/O_3") (pintype "bidirectional"))
      (node (ref "J43") (pin "30") (pinfunction "I/O_30") (pintype "bidirectional"))
      (node (ref "J43") (pin "31") (pinfunction "I/O_31") (pintype "bidirectional"))
      (node (ref "J43") (pin "35") (pinfunction "I/O_35") (pintype "bidirectional"))
      (node (ref "J43") (pin "36") (pinfunction "I/O_36") (pintype "bidirectional"))
      (node (ref "J43") (pin "39") (pinfunction "I/O_39") (pintype "bidirectional"))
      (node (ref "J43") (pin "40") (pinfunction "I/O_40") (pintype "bidirectional"))
      (node (ref "J43") (pin "43") (pinfunction "I/O_43") (pintype "bidirectional"))
      (node (ref "J43") (pin "44") (pinfunction "I/O_44") (pintype "bidirectional"))
      (node (ref "J43") (pin "47") (pinfunction "I/O_47") (pintype "bidirectional"))
      (node (ref "J43") (pin "48") (pinfunction "I/O_48") (pintype "bidirectional"))
      (node (ref "J43") (pin "51") (pinfunction "I/O_51") (pintype "bidirectional"))
      (node (ref "J43") (pin "52") (pinfunction "I/O_52") (pintype "bidirectional"))
      (node (ref "J43") (pin "55") (pinfunction "I/O_55") (pintype "bidirectional"))
      (node (ref "J43") (pin "56") (pinfunction "I/O_56") (pintype "bidirectional"))
      (node (ref "J43") (pin "59") (pinfunction "I/O_59") (pintype "bidirectional"))
      (node (ref "J43") (pin "6") (pinfunction "I/O_6") (pintype "bidirectional"))
      (node (ref "J43") (pin "60") (pinfunction "I/O_60") (pintype "bidirectional"))
      (node (ref "J43") (pin "63") (pinfunction "I/O_63") (pintype "bidirectional"))
      (node (ref "J43") (pin "64") (pinfunction "I/O_64") (pintype "bidirectional"))
      (node (ref "J43") (pin "7") (pinfunction "I/O_7") (pintype "bidirectional"))
      (node (ref "J44") (pin "10") (pinfunction "I/O_10") (pintype "bidirectional"))
      (node (ref "J44") (pin "11") (pinfunction "I/O_11") (pintype "bidirectional"))
      (node (ref "J44") (pin "14") (pinfunction "I/O_14") (pintype "bidirectional"))
      (node (ref "J44") (pin "15") (pinfunction "I/O_15") (pintype "bidirectional"))
      (node (ref "J44") (pin "18") (pinfunction "I/O_18") (pintype "bidirectional"))
      (node (ref "J44") (pin "19") (pinfunction "I/O_19") (pintype "bidirectional"))
      (node (ref "J44") (pin "2") (pinfunction "I/O_2") (pintype "bidirectional"))
      (node (ref "J44") (pin "22") (pinfunction "I/O_22") (pintype "bidirectional"))
      (node (ref "J44") (pin "23") (pinfunction "I/O_23") (pintype "bidirectional"))
      (node (ref "J44") (pin "26") (pinfunction "I/O_26") (pintype "bidirectional"))
      (node (ref "J44") (pin "27") (pinfunction "I/O_27") (pintype "bidirectional"))
      (node (ref "J44") (pin "3") (pinfunction "I/O_3") (pintype "bidirectional"))
      (node (ref "J44") (pin "30") (pinfunction "I/O_30") (pintype "bidirectional"))
      (node (ref "J44") (pin "31") (pinfunction "I/O_31") (pintype "bidirectional"))
      (node (ref "J44") (pin "34") (pinfunction "I/O_34") (pintype "bidirectional"))
      (node (ref "J44") (pin "35") (pinfunction "I/O_35") (pintype "bidirectional"))
      (node (ref "J44") (pin "38") (pinfunction "I/O_38") (pintype "bidirectional"))
      (node (ref "J44") (pin "39") (pinfunction "I/O_39") (pintype "bidirectional"))
      (node (ref "J44") (pin "42") (pinfunction "I/O_42") (pintype "bidirectional"))
      (node (ref "J44") (pin "43") (pinfunction "I/O_43") (pintype "bidirectional"))
      (node (ref "J44") (pin "46") (pinfunction "I/O_46") (pintype "bidirectional"))
      (node (ref "J44") (pin "47") (pinfunction "I/O_47") (pintype "bidirectional"))
      (node (ref "J44") (pin "50") (pinfunction "I/O_50") (pintype "bidirectional"))
      (node (ref "J44") (pin "51") (pinfunction "I/O_51") (pintype "bidirectional"))
      (node (ref "J44") (pin "54") (pinfunction "I/O_54") (pintype "bidirectional"))
      (node (ref "J44") (pin "58") (pinfunction "I/O_58") (pintype "bidirectional"))
      (node (ref "J44") (pin "59") (pinfunction "I/O_59") (pintype "bidirectional"))
      (node (ref "J44") (pin "6") (pinfunction "I/O_6") (pintype "bidirectional"))
      (node (ref "J44") (pin "62") (pinfunction "I/O_62") (pintype "bidirectional"))
      (node (ref "J44") (pin "63") (pinfunction "I/O_63") (pintype "bidirectional"))
      (node (ref "J44") (pin "7") (pinfunction "I/O_7") (pintype "bidirectional"))
      (node (ref "J45") (pin "10") (pinfunction "I/O_10") (pintype "bidirectional"))
      (node (ref "J45") (pin "11") (pinfunction "I/O_11") (pintype "bidirectional"))
      (node (ref "J45") (pin "14") (pinfunction "I/O_14") (pintype "bidirectional"))
      (node (ref "J45") (pin "15") (pinfunction "I/O_15") (pintype "bidirectional"))
      (node (ref "J45") (pin "18") (pinfunction "I/O_18") (pintype "bidirectional"))
      (node (ref "J45") (pin "19") (pinfunction "I/O_19") (pintype "bidirectional"))
      (node (ref "J45") (pin "2") (pinfunction "I/O_2") (pintype "bidirectional"))
      (node (ref "J45") (pin "22") (pinfunction "I/O_22") (pintype "bidirectional"))
      (node (ref "J45") (pin "23") (pinfunction "I/O_23") (pintype "bidirectional"))
      (node (ref "J45") (pin "26") (pinfunction "I/O_26") (pintype "bidirectional"))
      (node (ref "J45") (pin "27") (pinfunction "I/O_27") (pintype "bidirectional"))
      (node (ref "J45") (pin "3") (pinfunction "I/O_3") (pintype "bidirectional"))
      (node (ref "J45") (pin "30") (pinfunction "I/O_30") (pintype "bidirectional"))
      (node (ref "J45") (pin "31") (pinfunction "I/O_31") (pintype "bidirectional"))
      (node (ref "J45") (pin "35") (pinfunction "I/O_35") (pintype "bidirectional"))
      (node (ref "J45") (pin "36") (pinfunction "I/O_36") (pintype "bidirectional"))
      (node (ref "J45") (pin "39") (pinfunction "I/O_39") (pintype "bidirectional"))
      (node (ref "J45") (pin "40") (pinfunction "I/O_40") (pintype "bidirectional"))
      (node (ref "J45") (pin "43") (pinfunction "I/O_43") (pintype "bidirectional"))
      (node (ref "J45") (pin "44") (pinfunction "I/O_44") (pintype "bidirectional"))
      (node (ref "J45") (pin "47") (pinfunction "I/O_47") (pintype "bidirectional"))
      (node (ref "J45") (pin "48") (pinfunction "I/O_48") (pintype "bidirectional"))
      (node (ref "J45") (pin "51") (pinfunction "I/O_51") (pintype "bidirectional"))
      (node (ref "J45") (pin "52") (pinfunction "I/O_52") (pintype "bidirectional"))
      (node (ref "J45") (pin "55") (pinfunction "I/O_55") (pintype "bidirectional"))
      (node (ref "J45") (pin "56") (pinfunction "I/O_56") (pintype "bidirectional"))
      (node (ref "J45") (pin "59") (pinfunction "I/O_59") (pintype "bidirectional"))
      (node (ref "J45") (pin "6") (pinfunction "I/O_6") (pintype "bidirectional"))
      (node (ref "J45") (pin "60") (pinfunction "I/O_60") (pintype "bidirectional"))
      (node (ref "J45") (pin "63") (pinfunction "I/O_63") (pintype "bidirectional"))
      (node (ref "J45") (pin "64") (pinfunction "I/O_64") (pintype "bidirectional"))
      (node (ref "J45") (pin "7") (pinfunction "I/O_7") (pintype "bidirectional"))
      (node (ref "R374") (pin "2") (pinfunction "2_2") (pintype "passive"))
      (node (ref "R375") (pin "2") (pinfunction "2_2") (pintype "passive"))
      (node (ref "R376") (pin "2") (pinfunction "2_2") (pintype "passive"))
      (node (ref "R377") (pin "1") (pinfunction "1_1") (pintype "passive"))
      (node (ref "R450") (pin "2") (pinfunction "2_2") (pintype "passive"))
      (node (ref "R451") (pin "2") (pinfunction "2_2") (pintype "passive"))
      (node (ref "R454") (pin "2") (pinfunction "2_2") (pintype "passive"))
      (node (ref "R455") (pin "1") (pinfunction "1_1") (pintype "passive"))
      (node (ref "R476") (pin "2") (pinfunction "2_2") (pintype "passive"))
      (node (ref "R477") (pin "2") (pinfunction "2_2") (pintype "passive"))
      (node (ref "R478") (pin "2") (pinfunction "2_2") (pintype "passive"))
      (node (ref "R479") (pin "1") (pinfunction "1_1") (pintype "passive"))
      (node (ref "R500") (pin "2") (pinfunction "2_2") (pintype "passive"))
      (node (ref "R501") (pin "2") (pinfunction "2_2") (pintype "passive"))
      (node (ref "R502") (pin "2") (pinfunction "2_2") (pintype "passive"))
      (node (ref "R503") (pin "1") (pinfunction "1_1") (pintype "passive"))
      (node (ref "R524") (pin "2") (pinfunction "2_2") (pintype "passive"))
      (node (ref "R525") (pin "2") (pinfunction "2_2") (pintype "passive"))
      (node (ref "R526") (pin "2") (pinfunction "2_2") (pintype "passive"))
      (node (ref "R527") (pin "1") (pinfunction "1_1") (pintype "passive"))
      (node (ref "U39") (pin "1") (pinfunction "DIR1_1") (pintype "passive"))
      (node (ref "U39") (pin "10") (pinfunction "GND_10") (pintype "passive"))
      (node (ref "U39") (pin "2") (pinfunction "DIR2_2") (pintype "passive"))
      (node (ref "U39") (pin "7") (pinfunction "DIR3_7") (pintype "passive"))
      (node (ref "U39") (pin "8") (pinfunction "DIR4_8") (pintype "passive"))
      (node (ref "U39") (pin "9") (pinfunction "~{OE}_9") (pintype "passive"))
      (node (ref "U57") (pin "10") (pinfunction "GND_10") (pintype "passive"))
      (node (ref "U57") (pin "9") (pinfunction "~{OE}_9") (pintype "passive"))
      (node (ref "U58") (pin "10") (pinfunction "GND_10") (pintype "passive"))
      (node (ref "U58") (pin "9") (pinfunction "~{OE}_9") (pintype "passive"))
      (node (ref "U80") (pin "1") (pinfunction "DIR1_1") (pintype "passive"))
      (node (ref "U80") (pin "10") (pinfunction "GND_10") (pintype "passive"))
      (node (ref "U80") (pin "2") (pinfunction "DIR2_2") (pintype "passive"))
      (node (ref "U80") (pin "7") (pinfunction "DIR3_7") (pintype "passive"))
      (node (ref "U80") (pin "8") (pinfunction "DIR4_8") (pintype "passive"))
      (node (ref "U80") (pin "9") (pinfunction "~{OE}_9") (pintype "passive"))
      (node (ref "U81") (pin "10") (pinfunction "GND_10") (pintype "passive"))
      (node (ref "U81") (pin "9") (pinfunction "~{OE}_9") (pintype "passive"))
      (node (ref "U82") (pin "10") (pinfunction "GND_10") (pintype "passive"))
      (node (ref "U82") (pin "9") (pinfunction "~{OE}_9") (pintype "passive"))
      (node (ref "U83") (pin "1") (pinfunction "DIR1_1") (pintype "passive"))
      (node (ref "U83") (pin "10") (pinfunction "GND_10") (pintype "passive"))
      (node (ref "U83") (pin "2") (pinfunction "DIR2_2") (pintype "passive"))
      (node (ref "U83") (pin "7") (pinfunction "DIR3_7") (pintype "passive"))
      (node (ref "U83") (pin "8") (pinfunction "DIR4_8") (pintype "passive"))
      (node (ref "U83") (pin "9") (pinfunction "~{OE}_9") (pintype "passive"))
      (node (ref "U84") (pin "10") (pinfunction "GND_10") (pintype "passive"))
      (node (ref "U84") (pin "9") (pinfunction "~{OE}_9") (pintype "passive"))
      (node (ref "U85") (pin "10") (pinfunction "GND_10") (pintype "passive"))
      (node (ref "U85") (pin "9") (pinfunction "~{OE}_9") (pintype "passive"))
      (node (ref "U86") (pin "1") (pinfunction "DIR1_1") (pintype "passive"))
      (node (ref "U86") (pin "10") (pinfunction "GND_10") (pintype "passive"))
      (node (ref "U86") (pin "2") (pinfunction "DIR2_2") (pintype "passive"))
      (node (ref "U86") (pin "7") (pinfunction "DIR3_7") (pintype "passive"))
      (node (ref "U86") (pin "8") (pinfunction "DIR4_8") (pintype "passive"))
      (node (ref "U86") (pin "9") (pinfunction "~{OE}_9") (pintype "passive"))
      (node (ref "U87") (pin "10") (pinfunction "GND_10") (pintype "passive"))
      (node (ref "U87") (pin "9") (pinfunction "~{OE}_9") (pintype "passive"))
      (node (ref "U88") (pin "10") (pinfunction "GND_10") (pintype "passive"))
      (node (ref "U88") (pin "9") (pinfunction "~{OE}_9") (pintype "passive"))
      (node (ref "U89") (pin "1") (pinfunction "DIR1_1") (pintype "passive"))
      (node (ref "U89") (pin "10") (pinfunction "GND_10") (pintype "passive"))
      (node (ref "U89") (pin "2") (pinfunction "DIR2_2") (pintype "passive"))
      (node (ref "U89") (pin "7") (pinfunction "DIR3_7") (pintype "passive"))
      (node (ref "U89") (pin "8") (pinfunction "DIR4_8") (pintype "passive"))
      (node (ref "U89") (pin "9") (pinfunction "~{OE}_9") (pintype "passive"))
      (node (ref "U90") (pin "10") (pinfunction "GND_10") (pintype "passive"))
      (node (ref "U90") (pin "9") (pinfunction "~{OE}_9") (pintype "passive"))
      (node (ref "U91") (pin "10") (pinfunction "GND_10") (pintype "passive"))
      (node (ref "U91") (pin "9") (pinfunction "~{OE}_9") (pintype "passive"))
    )
    (net (code "136") (name "Net-(J42-I{slash}O-Pad36)") (class "Default")
      (node (ref "J42") (pin "36") (pinfunction "I/O_36") (pintype "bidirectional"))
      (node (ref "L54") (pin "1") (pinfunction "1_1") (pintype "passive"))
    )
    (net (code "137") (name "Net-(J42-I{slash}O-Pad40)") (class "Default")
      (node (ref "J42") (pin "40") (pinfunction "I/O_40") (pintype "bidirectional"))
      (node (ref "L55") (pin "1") (pinfunction "1_1") (pintype "passive"))
    )
    (net (code "138") (name "Net-(J42-I{slash}O-Pad44)") (class "Default")
      (node (ref "J42") (pin "44") (pinfunction "I/O_44") (pintype "bidirectional"))
      (node (ref "L68") (pin "1") (pinfunction "1_1") (pintype "passive"))
    )
    (net (code "139") (name "Net-(J42-I{slash}O-Pad48)") (class "Default")
      (node (ref "J42") (pin "48") (pinfunction "I/O_48") (pintype "bidirectional"))
      (node (ref "L69") (pin "1") (pinfunction "1_1") (pintype "passive"))
    )
    (net (code "140") (name "Net-(J42-I{slash}O-Pad52)") (class "Default")
      (node (ref "J42") (pin "52") (pinfunction "I/O_52") (pintype "bidirectional"))
      (node (ref "L70") (pin "1") (pinfunction "1_1") (pintype "passive"))
    )
    (net (code "141") (name "Net-(J42-I{slash}O-Pad56)") (class "Default")
      (node (ref "J42") (pin "56") (pinfunction "I/O_56") (pintype "bidirectional"))
      (node (ref "L71") (pin "1") (pinfunction "1_1") (pintype "passive"))
    )
    (net (code "142") (name "Net-(J42-I{slash}O-Pad60)") (class "Default")
      (node (ref "J42") (pin "60") (pinfunction "I/O_60") (pintype "bidirectional"))
      (node (ref "L72") (pin "1") (pinfunction "1_1") (pintype "passive"))
    )
    (net (code "143") (name "Net-(J42-I{slash}O-Pad64)") (class "Default")
      (node (ref "J42") (pin "64") (pinfunction "I/O_64") (pintype "bidirectional"))
      (node (ref "L73") (pin "1") (pinfunction "1_1") (pintype "passive"))
    )
    (net (code "144") (name "Net-(J43-I{slash}O-Pad34)") (class "Default")
      (node (ref "J43") (pin "34") (pinfunction "I/O_34") (pintype "bidirectional"))
      (node (ref "L74") (pin "1") (pinfunction "1_1") (pintype "passive"))
    )
    (net (code "145") (name "Net-(J43-I{slash}O-Pad38)") (class "Default")
      (node (ref "J43") (pin "38") (pinfunction "I/O_38") (pintype "bidirectional"))
      (node (ref "L75") (pin "1") (pinfunction "1_1") (pintype "passive"))
    )
    (net (code "146") (name "Net-(J43-I{slash}O-Pad42)") (class "Default")
      (node (ref "J43") (pin "42") (pinfunction "I/O_42") (pintype "bidirectional"))
      (node (ref "L76") (pin "1") (pinfunction "1_1") (pintype "passive"))
    )
    (net (code "147") (name "Net-(J43-I{slash}O-Pad46)") (class "Default")
      (node (ref "J43") (pin "46") (pinfunction "I/O_46") (pintype "bidirectional"))
      (node (ref "L77") (pin "1") (pinfunction "1_1") (pintype "passive"))
    )
    (net (code "148") (name "Net-(J43-I{slash}O-Pad50)") (class "Default")
      (node (ref "J43") (pin "50") (pinfunction "I/O_50") (pintype "bidirectional"))
      (node (ref "L78") (pin "1") (pinfunction "1_1") (pintype "passive"))
    )
    (net (code "149") (name "Net-(J43-I{slash}O-Pad54)") (class "Default")
      (node (ref "J43") (pin "54") (pinfunction "I/O_54") (pintype "bidirectional"))
      (node (ref "L79") (pin "1") (pinfunction "1_1") (pintype "passive"))
    )
    (net (code "150") (name "Net-(J43-I{slash}O-Pad58)") (class "Default")
      (node (ref "J43") (pin "58") (pinfunction "I/O_58") (pintype "bidirectional"))
      (node (ref "L81") (pin "1") (pinfunction "1_1") (pintype "passive"))
    )
    (net (code "151") (name "Net-(J43-I{slash}O-Pad62)") (class "Default")
      (node (ref "J43") (pin "62") (pinfunction "I/O_62") (pintype "bidirectional"))
      (node (ref "L82") (pin "1") (pinfunction "1_1") (pintype "passive"))
    )
    (net (code "152") (name "Net-(J44-I{slash}O-Pad36)") (class "Default")
      (node (ref "J44") (pin "36") (pinfunction "I/O_36") (pintype "bidirectional"))
      (node (ref "L83") (pin "1") (pinfunction "1_1") (pintype "passive"))
    )
    (net (code "153") (name "Net-(J44-I{slash}O-Pad40)") (class "Default")
      (node (ref "J44") (pin "40") (pinfunction "I/O_40") (pintype "bidirectional"))
      (node (ref "L84") (pin "1") (pinfunction "1_1") (pintype "passive"))
    )
    (net (code "154") (name "Net-(J44-I{slash}O-Pad44)") (class "Default")
      (node (ref "J44") (pin "44") (pinfunction "I/O_44") (pintype "bidirectional"))
      (node (ref "L85") (pin "1") (pinfunction "1_1") (pintype "passive"))
    )
    (net (code "155") (name "Net-(J44-I{slash}O-Pad48)") (class "Default")
      (node (ref "J44") (pin "48") (pinfunction "I/O_48") (pintype "bidirectional"))
      (node (ref "L86") (pin "1") (pinfunction "1_1") (pintype "passive"))
    )
    (net (code "156") (name "Net-(J44-I{slash}O-Pad52)") (class "Default")
      (node (ref "J44") (pin "52") (pinfunction "I/O_52") (pintype "bidirectional"))
      (node (ref "L87") (pin "1") (pinfunction "1_1") (pintype "passive"))
    )
    (net (code "157") (name "Net-(J44-I{slash}O-Pad56)") (class "Default")
      (node (ref "J44") (pin "56") (pinfunction "I/O_56") (pintype "bidirectional"))
      (node (ref "L88") (pin "1") (pinfunction "1_1") (pintype "passive"))
    )
    (net (code "158") (name "Net-(J44-I{slash}O-Pad60)") (class "Default")
      (node (ref "J44") (pin "60") (pinfunction "I/O_60") (pintype "bidirectional"))
      (node (ref "L89") (pin "1") (pinfunction "1_1") (pintype "passive"))
    )
    (net (code "159") (name "Net-(J44-I{slash}O-Pad64)") (class "Default")
      (node (ref "J44") (pin "64") (pinfunction "I/O_64") (pintype "bidirectional"))
      (node (ref "L90") (pin "1") (pinfunction "1_1") (pintype "passive"))
    )
    (net (code "160") (name "Net-(J45-I{slash}O-Pad34)") (class "Default")
      (node (ref "J45") (pin "34") (pinfunction "I/O_34") (pintype "bidirectional"))
      (node (ref "L91") (pin "1") (pinfunction "1_1") (pintype "passive"))
    )
    (net (code "161") (name "Net-(J45-I{slash}O-Pad38)") (class "Default")
      (node (ref "J45") (pin "38") (pinfunction "I/O_38") (pintype "bidirectional"))
      (node (ref "L92") (pin "1") (pinfunction "1_1") (pintype "passive"))
    )
    (net (code "162") (name "Net-(J45-I{slash}O-Pad42)") (class "Default")
      (node (ref "J45") (pin "42") (pinfunction "I/O_42") (pintype "bidirectional"))
      (node (ref "L93") (pin "2") (pinfunction "2_2") (pintype "passive"))
    )
    (net (code "163") (name "Net-(J45-I{slash}O-Pad46)") (class "Default")
      (node (ref "J45") (pin "46") (pinfunction "I/O_46") (pintype "bidirectional"))
      (node (ref "L94") (pin "2") (pinfunction "2_2") (pintype "passive"))
    )
    (net (code "164") (name "Net-(J45-I{slash}O-Pad50)") (class "Default")
      (node (ref "J45") (pin "50") (pinfunction "I/O_50") (pintype "bidirectional"))
      (node (ref "L95") (pin "1") (pinfunction "1_1") (pintype "passive"))
    )
    (net (code "165") (name "Net-(J45-I{slash}O-Pad54)") (class "Default")
      (node (ref "J45") (pin "54") (pinfunction "I/O_54") (pintype "bidirectional"))
      (node (ref "L96") (pin "1") (pinfunction "1_1") (pintype "passive"))
    )
    (net (code "166") (name "Net-(J45-I{slash}O-Pad58)") (class "Default")
      (node (ref "J45") (pin "58") (pinfunction "I/O_58") (pintype "bidirectional"))
      (node (ref "L97") (pin "1") (pinfunction "1_1") (pintype "passive"))
    )
    (net (code "167") (name "Net-(J45-I{slash}O-Pad62)") (class "Default")
      (node (ref "J45") (pin "62") (pinfunction "I/O_62") (pintype "bidirectional"))
      (node (ref "L98") (pin "1") (pinfunction "1_1") (pintype "passive"))
    )
    (net (code "168") (name "Net-(U39-B1)") (class "Default")
      (node (ref "R351") (pin "1") (pinfunction "1_1") (pintype "passive"))
      (node (ref "U39") (pin "14") (pinfunction "B1_14") (pintype "passive"))
    )
    (net (code "169") (name "Net-(U39-B2)") (class "Default")
      (node (ref "R356") (pin "1") (pinfunction "1_1") (pintype "passive"))
      (node (ref "U39") (pin "13") (pinfunction "B2_13") (pintype "passive"))
    )
    (net (code "170") (name "Net-(U39-B3)") (class "Default")
      (node (ref "R361") (pin "1") (pinfunction "1_1") (pintype "passive"))
      (node (ref "U39") (pin "12") (pinfunction "B3_12") (pintype "passive"))
    )
    (net (code "171") (name "Net-(U39-B4)") (class "Default")
      (node (ref "R366") (pin "1") (pinfunction "1_1") (pintype "passive"))
      (node (ref "U39") (pin "11") (pinfunction "B4_11") (pintype "passive"))
    )
    (net (code "172") (name "Net-(U57-B1)") (class "Default")
      (node (ref "R352") (pin "1") (pinfunction "1_1") (pintype "passive"))
      (node (ref "U57") (pin "14") (pinfunction "B1_14") (pintype "passive"))
    )
    (net (code "173") (name "Net-(U57-B2)") (class "Default")
      (node (ref "R357") (pin "1") (pinfunction "1_1") (pintype "passive"))
      (node (ref "U57") (pin "13") (pinfunction "B2_13") (pintype "passive"))
    )
    (net (code "174") (name "Net-(U57-B3)") (class "Default")
      (node (ref "R362") (pin "1") (pinfunction "1_1") (pintype "passive"))
      (node (ref "U57") (pin "12") (pinfunction "B3_12") (pintype "passive"))
    )
    (net (code "175") (name "Net-(U57-B4)") (class "Default")
      (node (ref "R367") (pin "1") (pinfunction "1_1") (pintype "passive"))
      (node (ref "U57") (pin "11") (pinfunction "B4_11") (pintype "passive"))
    )
    (net (code "176") (name "Net-(U57-DIR1)") (class "Default")
      (node (ref "R354") (pin "2") (pinfunction "2_2") (pintype "passive"))
      (node (ref "U57") (pin "1") (pinfunction "DIR1_1") (pintype "passive"))
    )
    (net (code "177") (name "Net-(U57-DIR2)") (class "Default")
      (node (ref "R359") (pin "2") (pinfunction "2_2") (pintype "passive"))
      (node (ref "U57") (pin "2") (pinfunction "DIR2_2") (pintype "passive"))
    )
    (net (code "178") (name "Net-(U57-DIR3)") (class "Default")
      (node (ref "R364") (pin "2") (pinfunction "2_2") (pintype "passive"))
      (node (ref "U57") (pin "7") (pinfunction "DIR3_7") (pintype "passive"))
    )
    (net (code "179") (name "Net-(U57-DIR4)") (class "Default")
      (node (ref "R369") (pin "2") (pinfunction "2_2") (pintype "passive"))
      (node (ref "U57") (pin "8") (pinfunction "DIR4_8") (pintype "passive"))
    )
    (net (code "180") (name "Net-(U58-B1)") (class "Default")
      (node (ref "R353") (pin "1") (pinfunction "1_1") (pintype "passive"))
      (node (ref "U58") (pin "14") (pinfunction "B1_14") (pintype "passive"))
    )
    (net (code "181") (name "Net-(U58-B2)") (class "Default")
      (node (ref "R358") (pin "1") (pinfunction "1_1") (pintype "passive"))
      (node (ref "U58") (pin "13") (pinfunction "B2_13") (pintype "passive"))
    )
    (net (code "182") (name "Net-(U58-B3)") (class "Default")
      (node (ref "R363") (pin "1") (pinfunction "1_1") (pintype "passive"))
      (node (ref "U58") (pin "12") (pinfunction "B3_12") (pintype "passive"))
    )
    (net (code "183") (name "Net-(U58-B4)") (class "Default")
      (node (ref "R368") (pin "1") (pinfunction "1_1") (pintype "passive"))
      (node (ref "U58") (pin "11") (pinfunction "B4_11") (pintype "passive"))
    )
    (net (code "184") (name "Net-(U58-DIR1)") (class "Default")
      (node (ref "R355") (pin "2") (pinfunction "2_2") (pintype "passive"))
      (node (ref "R377") (pin "2") (pinfunction "2_2") (pintype "passive"))
      (node (ref "U58") (pin "1") (pinfunction "DIR1_1") (pintype "passive"))
    )
    (net (code "185") (name "Net-(U58-DIR2)") (class "Default")
      (node (ref "R360") (pin "2") (pinfunction "2_2") (pintype "passive"))
      (node (ref "R376") (pin "1") (pinfunction "1_1") (pintype "passive"))
      (node (ref "U58") (pin "2") (pinfunction "DIR2_2") (pintype "passive"))
    )
    (net (code "186") (name "Net-(U58-DIR3)") (class "Default")
      (node (ref "R365") (pin "2") (pinfunction "2_2") (pintype "passive"))
      (node (ref "R375") (pin "1") (pinfunction "1_1") (pintype "passive"))
      (node (ref "U58") (pin "7") (pinfunction "DIR3_7") (pintype "passive"))
    )
    (net (code "187") (name "Net-(U58-DIR4)") (class "Default")
      (node (ref "R373") (pin "2") (pinfunction "2_2") (pintype "passive"))
      (node (ref "R374") (pin "1") (pinfunction "1_1") (pintype "passive"))
      (node (ref "U58") (pin "8") (pinfunction "DIR4_8") (pintype "passive"))
    )
    (net (code "188") (name "Net-(U80-B1)") (class "Default")
      (node (ref "R153") (pin "1") (pinfunction "1_1") (pintype "passive"))
      (node (ref "U80") (pin "14") (pinfunction "B1_14") (pintype "passive"))
    )
    (net (code "189") (name "Net-(U80-B2)") (class "Default")
      (node (ref "R209") (pin "1") (pinfunction "1_1") (pintype "passive"))
      (node (ref "U80") (pin "13") (pinfunction "B2_13") (pintype "passive"))
    )
    (net (code "190") (name "Net-(U80-B3)") (class "Default")
      (node (ref "R256") (pin "1") (pinfunction "1_1") (pintype "passive"))
      (node (ref "U80") (pin "12") (pinfunction "B3_12") (pintype "passive"))
    )
    (net (code "191") (name "Net-(U80-B4)") (class "Default")
      (node (ref "R445") (pin "1") (pinfunction "1_1") (pintype "passive"))
      (node (ref "U80") (pin "11") (pinfunction "B4_11") (pintype "passive"))
    )
    (net (code "192") (name "Net-(U81-B1)") (class "Default")
      (node (ref "R182") (pin "1") (pinfunction "1_1") (pintype "passive"))
      (node (ref "U81") (pin "14") (pinfunction "B1_14") (pintype "passive"))
    )
    (net (code "193") (name "Net-(U81-B2)") (class "Default")
      (node (ref "R220") (pin "1") (pinfunction "1_1") (pintype "passive"))
      (node (ref "U81") (pin "13") (pinfunction "B2_13") (pintype "passive"))
    )
    (net (code "194") (name "Net-(U81-B3)") (class "Default")
      (node (ref "R437") (pin "1") (pinfunction "1_1") (pintype "passive"))
      (node (ref "U81") (pin "12") (pinfunction "B3_12") (pintype "passive"))
    )
    (net (code "195") (name "Net-(U81-B4)") (class "Default")
      (node (ref "R446") (pin "1") (pinfunction "1_1") (pintype "passive"))
      (node (ref "U81") (pin "11") (pinfunction "B4_11") (pintype "passive"))
    )
    (net (code "196") (name "Net-(U81-DIR1)") (class "Default")
      (node (ref "R192") (pin "2") (pinfunction "2_2") (pintype "passive"))
      (node (ref "U81") (pin "1") (pinfunction "DIR1_1") (pintype "passive"))
    )
    (net (code "197") (name "Net-(U81-DIR2)") (class "Default")
      (node (ref "R240") (pin "2") (pinfunction "2_2") (pintype "passive"))
      (node (ref "U81") (pin "2") (pinfunction "DIR2_2") (pintype "passive"))
    )
    (net (code "198") (name "Net-(U81-DIR3)") (class "Default")
      (node (ref "R442") (pin "2") (pinfunction "2_2") (pintype "passive"))
      (node (ref "U81") (pin "7") (pinfunction "DIR3_7") (pintype "passive"))
    )
    (net (code "199") (name "Net-(U81-DIR4)") (class "Default")
      (node (ref "R448") (pin "2") (pinfunction "2_2") (pintype "passive"))
      (node (ref "U81") (pin "8") (pinfunction "DIR4_8") (pintype "passive"))
    )
    (net (code "200") (name "Net-(U82-B1)") (class "Default")
      (node (ref "R183") (pin "1") (pinfunction "1_1") (pintype "passive"))
      (node (ref "U82") (pin "14") (pinfunction "B1_14") (pintype "passive"))
    )
    (net (code "201") (name "Net-(U82-B2)") (class "Default")
      (node (ref "R238") (pin "1") (pinfunction "1_1") (pintype "passive"))
      (node (ref "U82") (pin "13") (pinfunction "B2_13") (pintype "passive"))
    )
    (net (code "202") (name "Net-(U82-B3)") (class "Default")
      (node (ref "R438") (pin "1") (pinfunction "1_1") (pintype "passive"))
      (node (ref "U82") (pin "12") (pinfunction "B3_12") (pintype "passive"))
    )
    (net (code "203") (name "Net-(U82-B4)") (class "Default")
      (node (ref "R447") (pin "1") (pinfunction "1_1") (pintype "passive"))
      (node (ref "U82") (pin "11") (pinfunction "B4_11") (pintype "passive"))
    )
    (net (code "204") (name "Net-(U82-DIR1)") (class "Default")
      (node (ref "R207") (pin "2") (pinfunction "2_2") (pintype "passive"))
      (node (ref "R455") (pin "2") (pinfunction "2_2") (pintype "passive"))
      (node (ref "U82") (pin "1") (pinfunction "DIR1_1") (pintype "passive"))
    )
    (net (code "205") (name "Net-(U82-DIR2)") (class "Default")
      (node (ref "R246") (pin "2") (pinfunction "2_2") (pintype "passive"))
      (node (ref "R454") (pin "1") (pinfunction "1_1") (pintype "passive"))
      (node (ref "U82") (pin "2") (pinfunction "DIR2_2") (pintype "passive"))
    )
    (net (code "206") (name "Net-(U82-DIR3)") (class "Default")
      (node (ref "R444") (pin "2") (pinfunction "2_2") (pintype "passive"))
      (node (ref "R451") (pin "1") (pinfunction "1_1") (pintype "passive"))
      (node (ref "U82") (pin "7") (pinfunction "DIR3_7") (pintype "passive"))
    )
    (net (code "207") (name "Net-(U82-DIR4)") (class "Default")
      (node (ref "R449") (pin "2") (pinfunction "2_2") (pintype "passive"))
      (node (ref "R450") (pin "1") (pinfunction "1_1") (pintype "passive"))
      (node (ref "U82") (pin "8") (pinfunction "DIR4_8") (pintype "passive"))
    )
    (net (code "208") (name "Net-(U83-B1)") (class "Default")
      (node (ref "R456") (pin "1") (pinfunction "1_1") (pintype "passive"))
      (node (ref "U83") (pin "14") (pinfunction "B1_14") (pintype "passive"))
    )
    (net (code "209") (name "Net-(U83-B2)") (class "Default")
      (node (ref "R461") (pin "1") (pinfunction "1_1") (pintype "passive"))
      (node (ref "U83") (pin "13") (pinfunction "B2_13") (pintype "passive"))
    )
    (net (code "210") (name "Net-(U83-B3)") (class "Default")
      (node (ref "R466") (pin "1") (pinfunction "1_1") (pintype "passive"))
      (node (ref "U83") (pin "12") (pinfunction "B3_12") (pintype "passive"))
    )
    (net (code "211") (name "Net-(U83-B4)") (class "Default")
      (node (ref "R471") (pin "1") (pinfunction "1_1") (pintype "passive"))
      (node (ref "U83") (pin "11") (pinfunction "B4_11") (pintype "passive"))
    )
    (net (code "212") (name "Net-(U84-B1)") (class "Default")
      (node (ref "R457") (pin "1") (pinfunction "1_1") (pintype "passive"))
      (node (ref "U84") (pin "14") (pinfunction "B1_14") (pintype "passive"))
    )
    (net (code "213") (name "Net-(U84-B2)") (class "Default")
      (node (ref "R462") (pin "2") (pinfunction "2_2") (pintype "passive"))
      (node (ref "U84") (pin "13") (pinfunction "B2_13") (pintype "passive"))
    )
    (net (code "214") (name "Net-(U84-B3)") (class "Default")
      (node (ref "R467") (pin "1") (pinfunction "1_1") (pintype "passive"))
      (node (ref "U84") (pin "12") (pinfunction "B3_12") (pintype "passive"))
    )
    (net (code "215") (name "Net-(U84-B4)") (class "Default")
      (node (ref "R472") (pin "1") (pinfunction "1_1") (pintype "passive"))
      (node (ref "U84") (pin "11") (pinfunction "B4_11") (pintype "passive"))
    )
    (net (code "216") (name "Net-(U84-DIR1)") (class "Default")
      (node (ref "R459") (pin "2") (pinfunction "2_2") (pintype "passive"))
      (node (ref "U84") (pin "1") (pinfunction "DIR1_1") (pintype "passive"))
    )
    (net (code "217") (name "Net-(U84-DIR2)") (class "Default")
      (node (ref "R464") (pin "2") (pinfunction "2_2") (pintype "passive"))
      (node (ref "U84") (pin "2") (pinfunction "DIR2_2") (pintype "passive"))
    )
    (net (code "218") (name "Net-(U84-DIR3)") (class "Default")
      (node (ref "R469") (pin "2") (pinfunction "2_2") (pintype "passive"))
      (node (ref "U84") (pin "7") (pinfunction "DIR3_7") (pintype "passive"))
    )
    (net (code "219") (name "Net-(U84-DIR4)") (class "Default")
      (node (ref "R474") (pin "2") (pinfunction "2_2") (pintype "passive"))
      (node (ref "U84") (pin "8") (pinfunction "DIR4_8") (pintype "passive"))
    )
    (net (code "220") (name "Net-(U85-B1)") (class "Default")
      (node (ref "R458") (pin "1") (pinfunction "1_1") (pintype "passive"))
      (node (ref "U85") (pin "14") (pinfunction "B1_14") (pintype "passive"))
    )
    (net (code "221") (name "Net-(U85-B2)") (class "Default")
      (node (ref "R463") (pin "1") (pinfunction "1_1") (pintype "passive"))
      (node (ref "U85") (pin "13") (pinfunction "B2_13") (pintype "passive"))
    )
    (net (code "222") (name "Net-(U85-B3)") (class "Default")
      (node (ref "R468") (pin "1") (pinfunction "1_1") (pintype "passive"))
      (node (ref "U85") (pin "12") (pinfunction "B3_12") (pintype "passive"))
    )
    (net (code "223") (name "Net-(U85-B4)") (class "Default")
      (node (ref "R473") (pin "1") (pinfunction "1_1") (pintype "passive"))
      (node (ref "U85") (pin "11") (pinfunction "B4_11") (pintype "passive"))
    )
    (net (code "224") (name "Net-(U85-DIR1)") (class "Default")
      (node (ref "R460") (pin "2") (pinfunction "2_2") (pintype "passive"))
      (node (ref "R479") (pin "2") (pinfunction "2_2") (pintype "passive"))
      (node (ref "U85") (pin "1") (pinfunction "DIR1_1") (pintype "passive"))
    )
    (net (code "225") (name "Net-(U85-DIR2)") (class "Default")
      (node (ref "R465") (pin "2") (pinfunction "2_2") (pintype "passive"))
      (node (ref "R478") (pin "1") (pinfunction "1_1") (pintype "passive"))
      (node (ref "U85") (pin "2") (pinfunction "DIR2_2") (pintype "passive"))
    )
    (net (code "226") (name "Net-(U85-DIR3)") (class "Default")
      (node (ref "R470") (pin "2") (pinfunction "2_2") (pintype "passive"))
      (node (ref "R477") (pin "1") (pinfunction "1_1") (pintype "passive"))
      (node (ref "U85") (pin "7") (pinfunction "DIR3_7") (pintype "passive"))
    )
    (net (code "227") (name "Net-(U85-DIR4)") (class "Default")
      (node (ref "R475") (pin "2") (pinfunction "2_2") (pintype "passive"))
      (node (ref "R476") (pin "1") (pinfunction "1_1") (pintype "passive"))
      (node (ref "U85") (pin "8") (pinfunction "DIR4_8") (pintype "passive"))
    )
    (net (code "228") (name "Net-(U86-B1)") (class "Default")
      (node (ref "R480") (pin "1") (pinfunction "1_1") (pintype "passive"))
      (node (ref "U86") (pin "14") (pinfunction "B1_14") (pintype "passive"))
    )
    (net (code "229") (name "Net-(U86-B2)") (class "Default")
      (node (ref "R483") (pin "1") (pinfunction "1_1") (pintype "passive"))
      (node (ref "U86") (pin "13") (pinfunction "B2_13") (pintype "passive"))
    )
    (net (code "230") (name "Net-(U86-B3)") (class "Default")
      (node (ref "R488") (pin "1") (pinfunction "1_1") (pintype "passive"))
      (node (ref "U86") (pin "12") (pinfunction "B3_12") (pintype "passive"))
    )
    (net (code "231") (name "Net-(U86-B4)") (class "Default")
      (node (ref "R493") (pin "1") (pinfunction "1_1") (pintype "passive"))
      (node (ref "U86") (pin "11") (pinfunction "B4_11") (pintype "passive"))
    )
    (net (code "232") (name "Net-(U87-B1)") (class "Default")
      (node (ref "R481") (pin "1") (pinfunction "1_1") (pintype "passive"))
      (node (ref "U87") (pin "14") (pinfunction "B1_14") (pintype "passive"))
    )
    (net (code "233") (name "Net-(U87-B2)") (class "Default")
      (node (ref "R486") (pin "1") (pinfunction "1_1") (pintype "passive"))
      (node (ref "U87") (pin "13") (pinfunction "B2_13") (pintype "passive"))
    )
    (net (code "234") (name "Net-(U87-B3)") (class "Default")
      (node (ref "R491") (pin "1") (pinfunction "1_1") (pintype "passive"))
      (node (ref "U87") (pin "12") (pinfunction "B3_12") (pintype "passive"))
    )
    (net (code "235") (name "Net-(U87-B4)") (class "Default")
      (node (ref "R496") (pin "1") (pinfunction "1_1") (pintype "passive"))
      (node (ref "U87") (pin "11") (pinfunction "B4_11") (pintype "passive"))
    )
    (net (code "236") (name "Net-(U87-DIR1)") (class "Default")
      (node (ref "R484") (pin "2") (pinfunction "2_2") (pintype "passive"))
      (node (ref "U87") (pin "1") (pinfunction "DIR1_1") (pintype "passive"))
    )
    (net (code "237") (name "Net-(U87-DIR2)") (class "Default")
      (node (ref "R489") (pin "2") (pinfunction "2_2") (pintype "passive"))
      (node (ref "U87") (pin "2") (pinfunction "DIR2_2") (pintype "passive"))
    )
    (net (code "238") (name "Net-(U87-DIR3)") (class "Default")
      (node (ref "R494") (pin "2") (pinfunction "2_2") (pintype "passive"))
      (node (ref "U87") (pin "7") (pinfunction "DIR3_7") (pintype "passive"))
    )
    (net (code "239") (name "Net-(U87-DIR4)") (class "Default")
      (node (ref "R498") (pin "2") (pinfunction "2_2") (pintype "passive"))
      (node (ref "U87") (pin "8") (pinfunction "DIR4_8") (pintype "passive"))
    )
    (net (code "240") (name "Net-(U88-B1)") (class "Default")
      (node (ref "R482") (pin "1") (pinfunction "1_1") (pintype "passive"))
      (node (ref "U88") (pin "14") (pinfunction "B1_14") (pintype "passive"))
    )
    (net (code "241") (name "Net-(U88-B2)") (class "Default")
      (node (ref "R487") (pin "1") (pinfunction "1_1") (pintype "passive"))
      (node (ref "U88") (pin "13") (pinfunction "B2_13") (pintype "passive"))
    )
    (net (code "242") (name "Net-(U88-B3)") (class "Default")
      (node (ref "R492") (pin "1") (pinfunction "1_1") (pintype "passive"))
      (node (ref "U88") (pin "12") (pinfunction "B3_12") (pintype "passive"))
    )
    (net (code "243") (name "Net-(U88-B4)") (class "Default")
      (node (ref "R497") (pin "1") (pinfunction "1_1") (pintype "passive"))
      (node (ref "U88") (pin "11") (pinfunction "B4_11") (pintype "passive"))
    )
    (net (code "244") (name "Net-(U88-DIR1)") (class "Default")
      (node (ref "R485") (pin "2") (pinfunction "2_2") (pintype "passive"))
      (node (ref "R503") (pin "2") (pinfunction "2_2") (pintype "passive"))
      (node (ref "U88") (pin "1") (pinfunction "DIR1_1") (pintype "passive"))
    )
    (net (code "245") (name "Net-(U88-DIR2)") (class "Default")
      (node (ref "R490") (pin "2") (pinfunction "2_2") (pintype "passive"))
      (node (ref "R502") (pin "1") (pinfunction "1_1") (pintype "passive"))
      (node (ref "U88") (pin "2") (pinfunction "DIR2_2") (pintype "passive"))
    )
    (net (code "246") (name "Net-(U88-DIR3)") (class "Default")
      (node (ref "R495") (pin "2") (pinfunction "2_2") (pintype "passive"))
      (node (ref "R501") (pin "1") (pinfunction "1_1") (pintype "passive"))
      (node (ref "U88") (pin "7") (pinfunction "DIR3_7") (pintype "passive"))
    )
    (net (code "247") (name "Net-(U88-DIR4)") (class "Default")
      (node (ref "R499") (pin "2") (pinfunction "2_2") (pintype "passive"))
      (node (ref "R500") (pin "1") (pinfunction "1_1") (pintype "passive"))
      (node (ref "U88") (pin "8") (pinfunction "DIR4_8") (pintype "passive"))
    )
    (net (code "248") (name "Net-(U89-B1)") (class "Default")
      (node (ref "R504") (pin "1") (pinfunction "1_1") (pintype "passive"))
      (node (ref "U89") (pin "14") (pinfunction "B1_14") (pintype "passive"))
    )
    (net (code "249") (name "Net-(U89-B2)") (class "Default")
      (node (ref "R505") (pin "1") (pinfunction "1_1") (pintype "passive"))
      (node (ref "U89") (pin "13") (pinfunction "B2_13") (pintype "passive"))
    )
    (net (code "250") (name "Net-(U89-B3)") (class "Default")
      (node (ref "R510") (pin "1") (pinfunction "1_1") (pintype "passive"))
      (node (ref "U89") (pin "12") (pinfunction "B3_12") (pintype "passive"))
    )
    (net (code "251") (name "Net-(U89-B4)") (class "Default")
      (node (ref "R515") (pin "1") (pinfunction "1_1") (pintype "passive"))
      (node (ref "U89") (pin "11") (pinfunction "B4_11") (pintype "passive"))
    )
    (net (code "252") (name "Net-(U90-B1)") (class "Default")
      (node (ref "R506") (pin "1") (pinfunction "1_1") (pintype "passive"))
      (node (ref "U90") (pin "14") (pinfunction "B1_14") (pintype "passive"))
    )
    (net (code "253") (name "Net-(U90-B2)") (class "Default")
      (node (ref "R511") (pin "1") (pinfunction "1_1") (pintype "passive"))
      (node (ref "U90") (pin "13") (pinfunction "B2_13") (pintype "passive"))
    )
    (net (code "254") (name "Net-(U90-B3)") (class "Default")
      (node (ref "R516") (pin "1") (pinfunction "1_1") (pintype "passive"))
      (node (ref "U90") (pin "12") (pinfunction "B3_12") (pintype "passive"))
    )
    (net (code "255") (name "Net-(U90-B4)") (class "Default")
      (node (ref "R520") (pin "1") (pinfunction "1_1") (pintype "passive"))
      (node (ref "U90") (pin "11") (pinfunction "B4_11") (pintype "passive"))
    )
    (net (code "256") (name "Net-(U90-DIR1)") (class "Default")
      (node (ref "R508") (pin "2") (pinfunction "2_2") (pintype "passive"))
      (node (ref "U90") (pin "1") (pinfunction "DIR1_1") (pintype "passive"))
    )
    (net (code "257") (name "Net-(U90-DIR2)") (class "Default")
      (node (ref "R513") (pin "2") (pinfunction "2_2") (pintype "passive"))
      (node (ref "U90") (pin "2") (pinfunction "DIR2_2") (pintype "passive"))
    )
    (net (code "258") (name "Net-(U90-DIR3)") (class "Default")
      (node (ref "R518") (pin "2") (pinfunction "2_2") (pintype "passive"))
      (node (ref "U90") (pin "7") (pinfunction "DIR3_7") (pintype "passive"))
    )
    (net (code "259") (name "Net-(U90-DIR4)") (class "Default")
      (node (ref "R522") (pin "2") (pinfunction "2_2") (pintype "passive"))
      (node (ref "U90") (pin "8") (pinfunction "DIR4_8") (pintype "passive"))
    )
    (net (code "260") (name "Net-(U91-B1)") (class "Default")
      (node (ref "R507") (pin "1") (pinfunction "1_1") (pintype "passive"))
      (node (ref "U91") (pin "14") (pinfunction "B1_14") (pintype "passive"))
    )
    (net (code "261") (name "Net-(U91-B2)") (class "Default")
      (node (ref "R512") (pin "1") (pinfunction "1_1") (pintype "passive"))
      (node (ref "U91") (pin "13") (pinfunction "B2_13") (pintype "passive"))
    )
    (net (code "262") (name "Net-(U91-B3)") (class "Default")
      (node (ref "R517") (pin "1") (pinfunction "1_1") (pintype "passive"))
      (node (ref "U91") (pin "12") (pinfunction "B3_12") (pintype "passive"))
    )
    (net (code "263") (name "Net-(U91-B4)") (class "Default")
      (node (ref "R521") (pin "1") (pinfunction "1_1") (pintype "passive"))
      (node (ref "U91") (pin "11") (pinfunction "B4_11") (pintype "passive"))
    )
    (net (code "264") (name "Net-(U91-DIR1)") (class "Default")
      (node (ref "R509") (pin "2") (pinfunction "2_2") (pintype "passive"))
      (node (ref "R527") (pin "2") (pinfunction "2_2") (pintype "passive"))
      (node (ref "U91") (pin "1") (pinfunction "DIR1_1") (pintype "passive"))
    )
    (net (code "265") (name "Net-(U91-DIR2)") (class "Default")
      (node (ref "R514") (pin "2") (pinfunction "2_2") (pintype "passive"))
      (node (ref "R526") (pin "1") (pinfunction "1_1") (pintype "passive"))
      (node (ref "U91") (pin "2") (pinfunction "DIR2_2") (pintype "passive"))
    )
    (net (code "266") (name "Net-(U91-DIR3)") (class "Default")
      (node (ref "R519") (pin "2") (pinfunction "2_2") (pintype "passive"))
      (node (ref "R525") (pin "1") (pinfunction "1_1") (pintype "passive"))
      (node (ref "U91") (pin "7") (pinfunction "DIR3_7") (pintype "passive"))
    )
    (net (code "267") (name "Net-(U91-DIR4)") (class "Default")
      (node (ref "R523") (pin "2") (pinfunction "2_2") (pintype "passive"))
      (node (ref "R524") (pin "1") (pinfunction "1_1") (pintype "passive"))
      (node (ref "U91") (pin "8") (pinfunction "DIR4_8") (pintype "passive"))
    )
    (net (code "268") (name "unconnected-(J44-I{slash}O-Pad55)") (class "Default")
      (node (ref "J44") (pin "55") (pinfunction "I/O_55") (pintype "bidirectional"))
    )
  )
)
